# Nixie_Clock.net
KiCad netlist of a schematic drawn in EAGLE
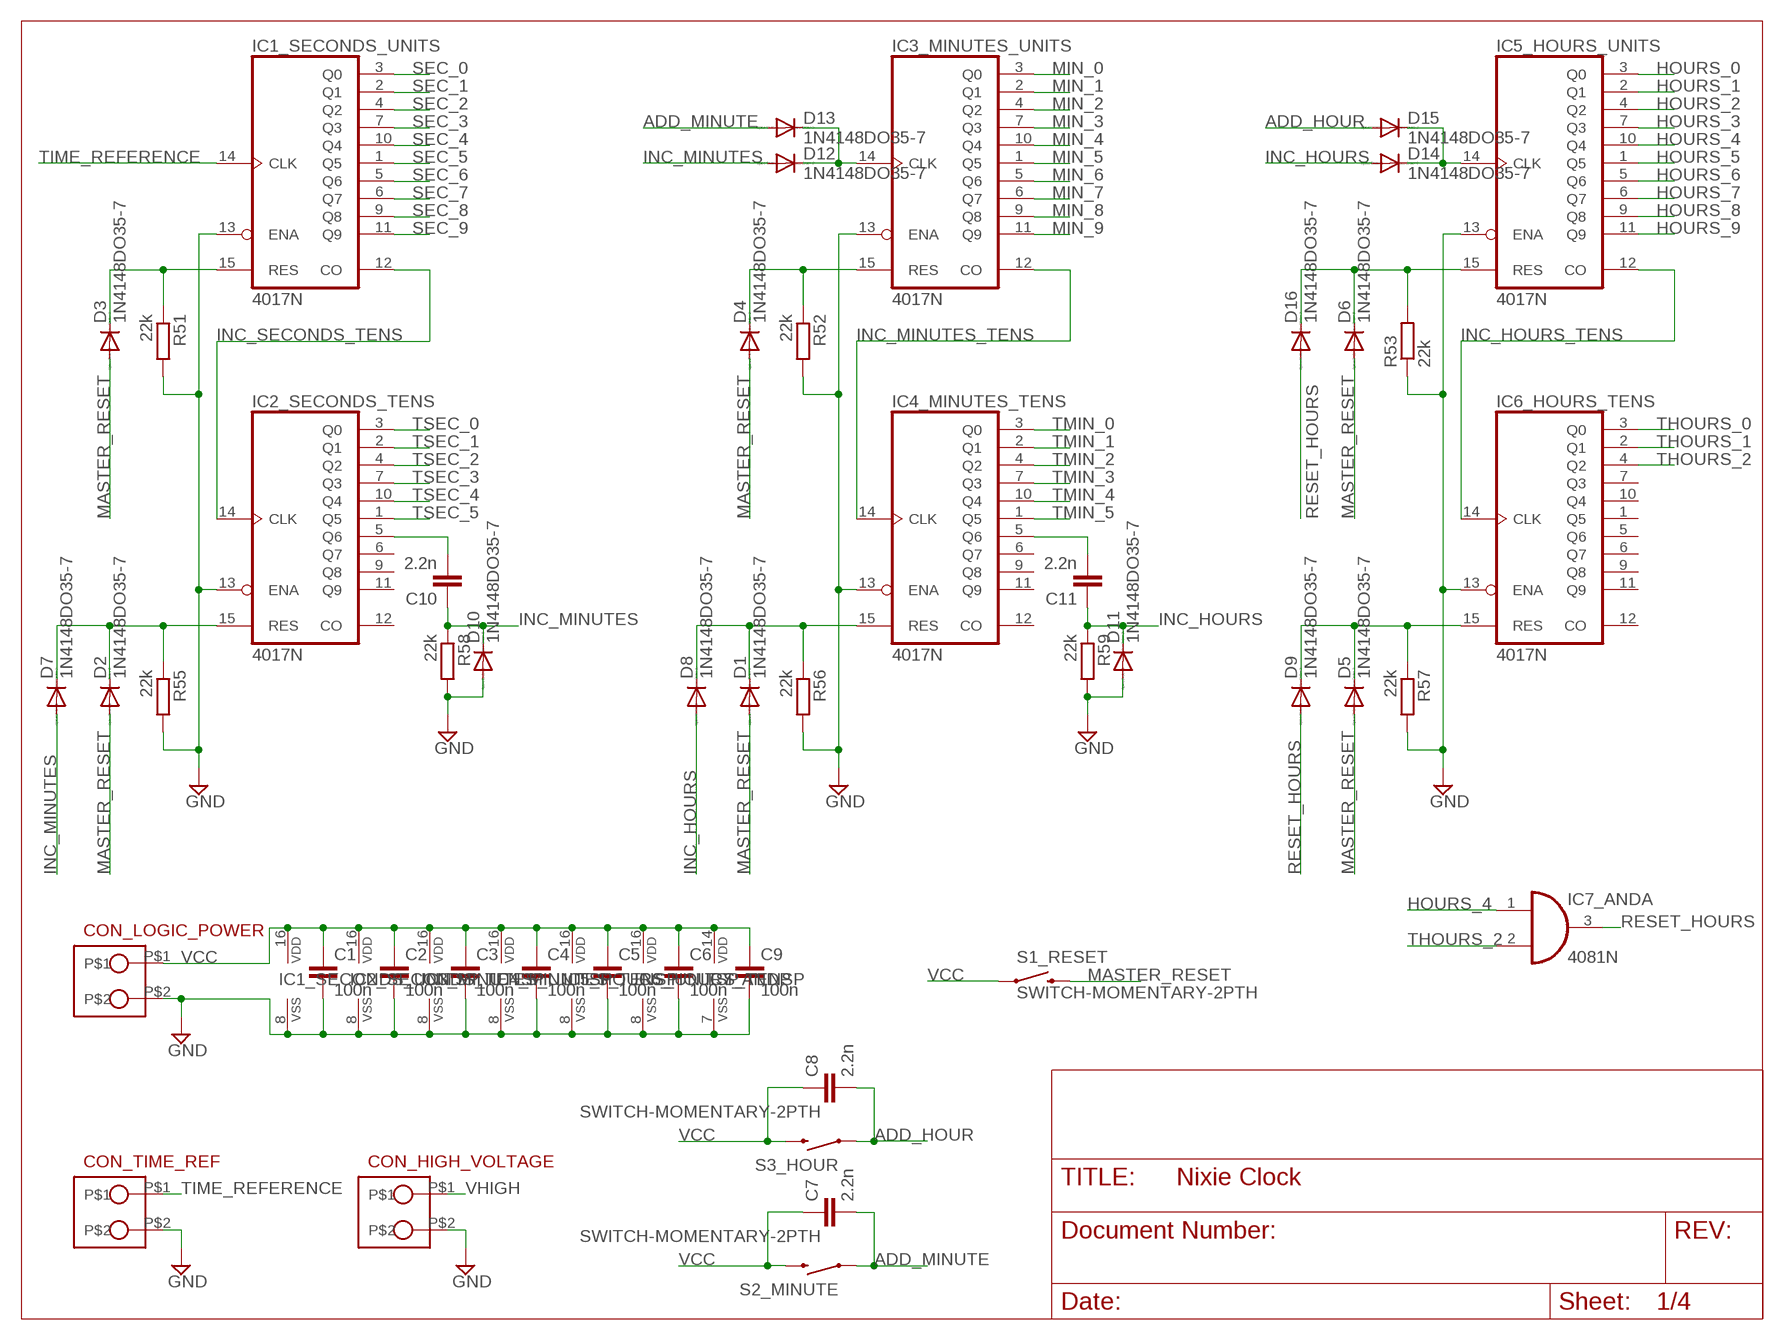
[diagram p0: schematic, sheet 1]
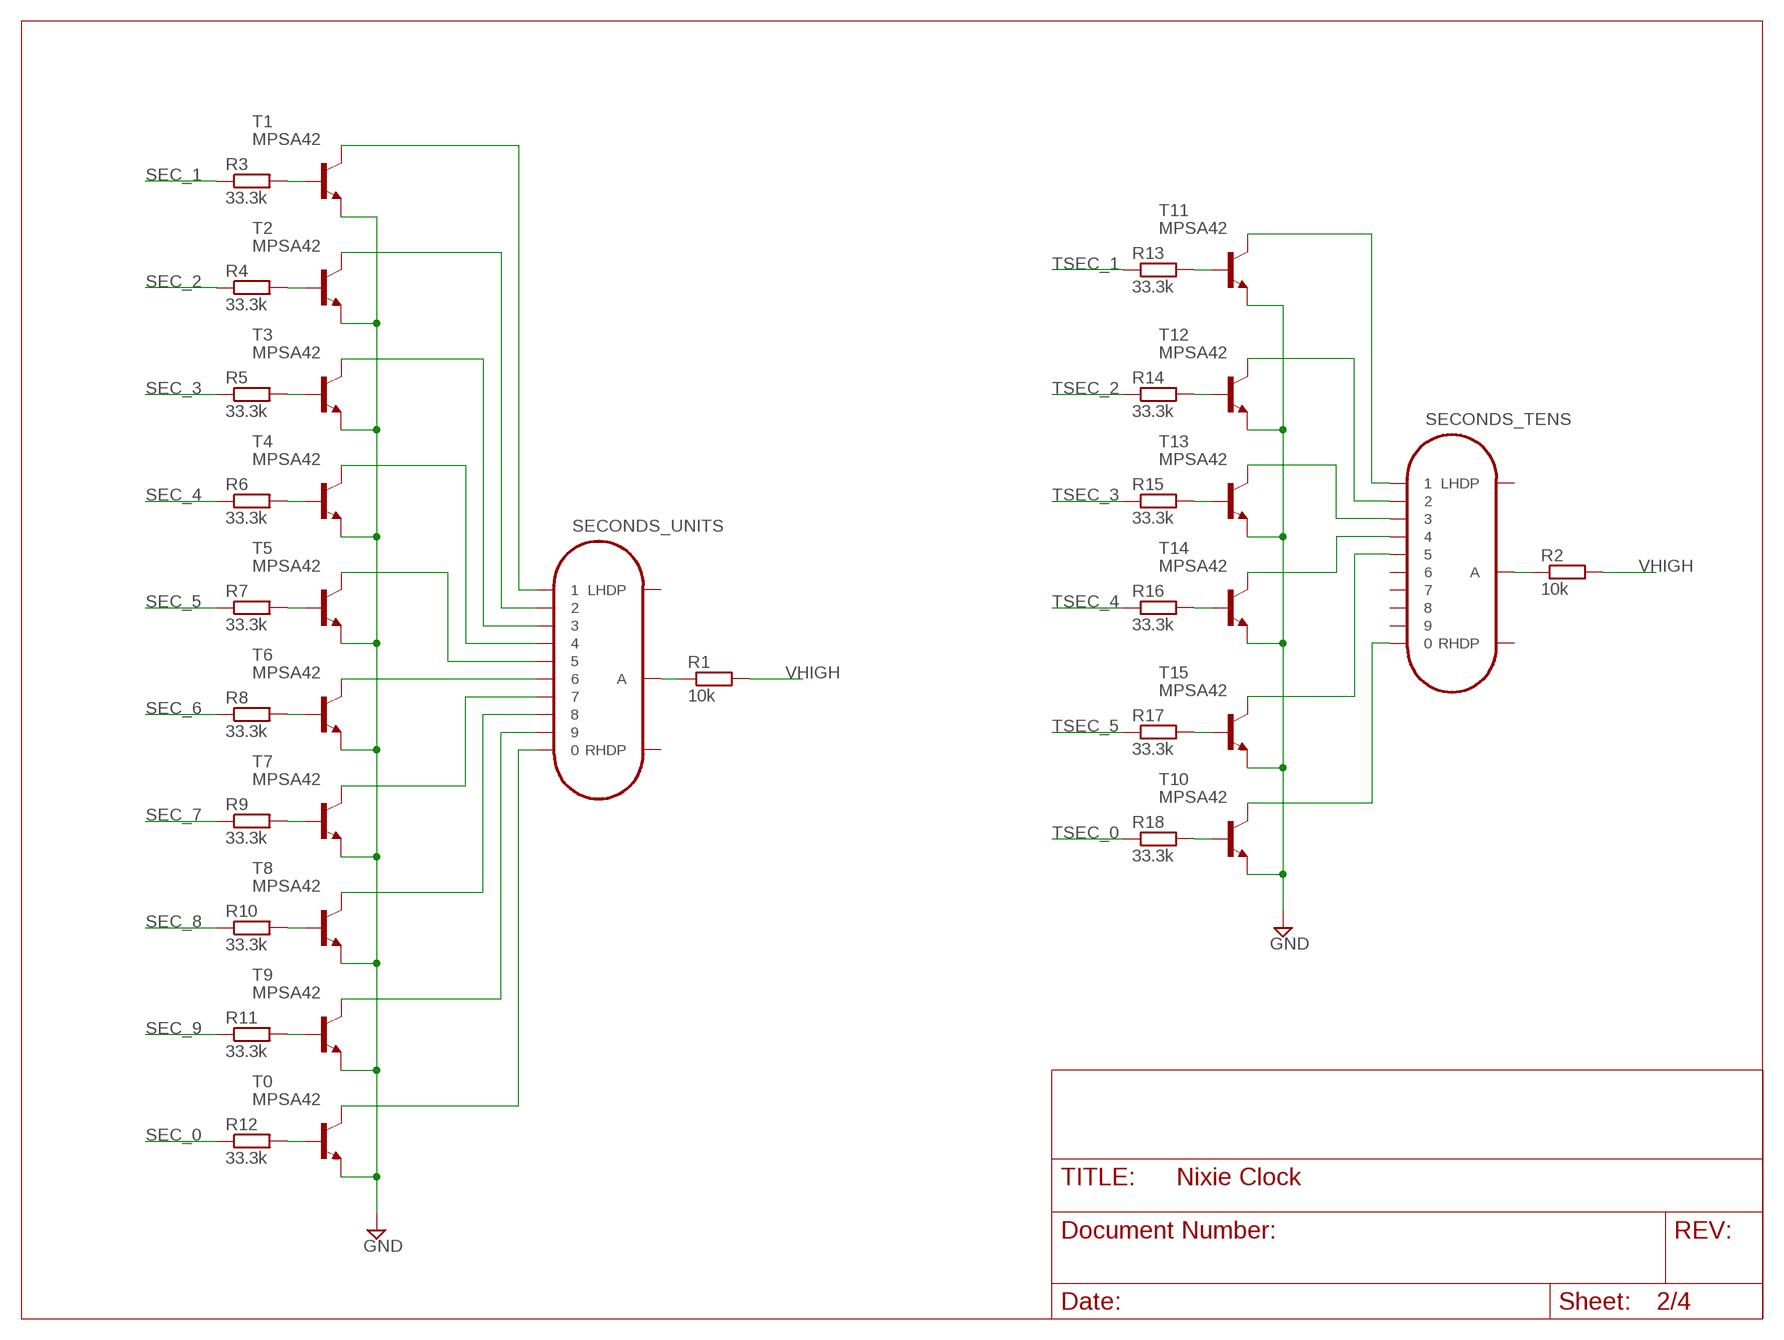
[diagram p1: schematic, sheet 2]
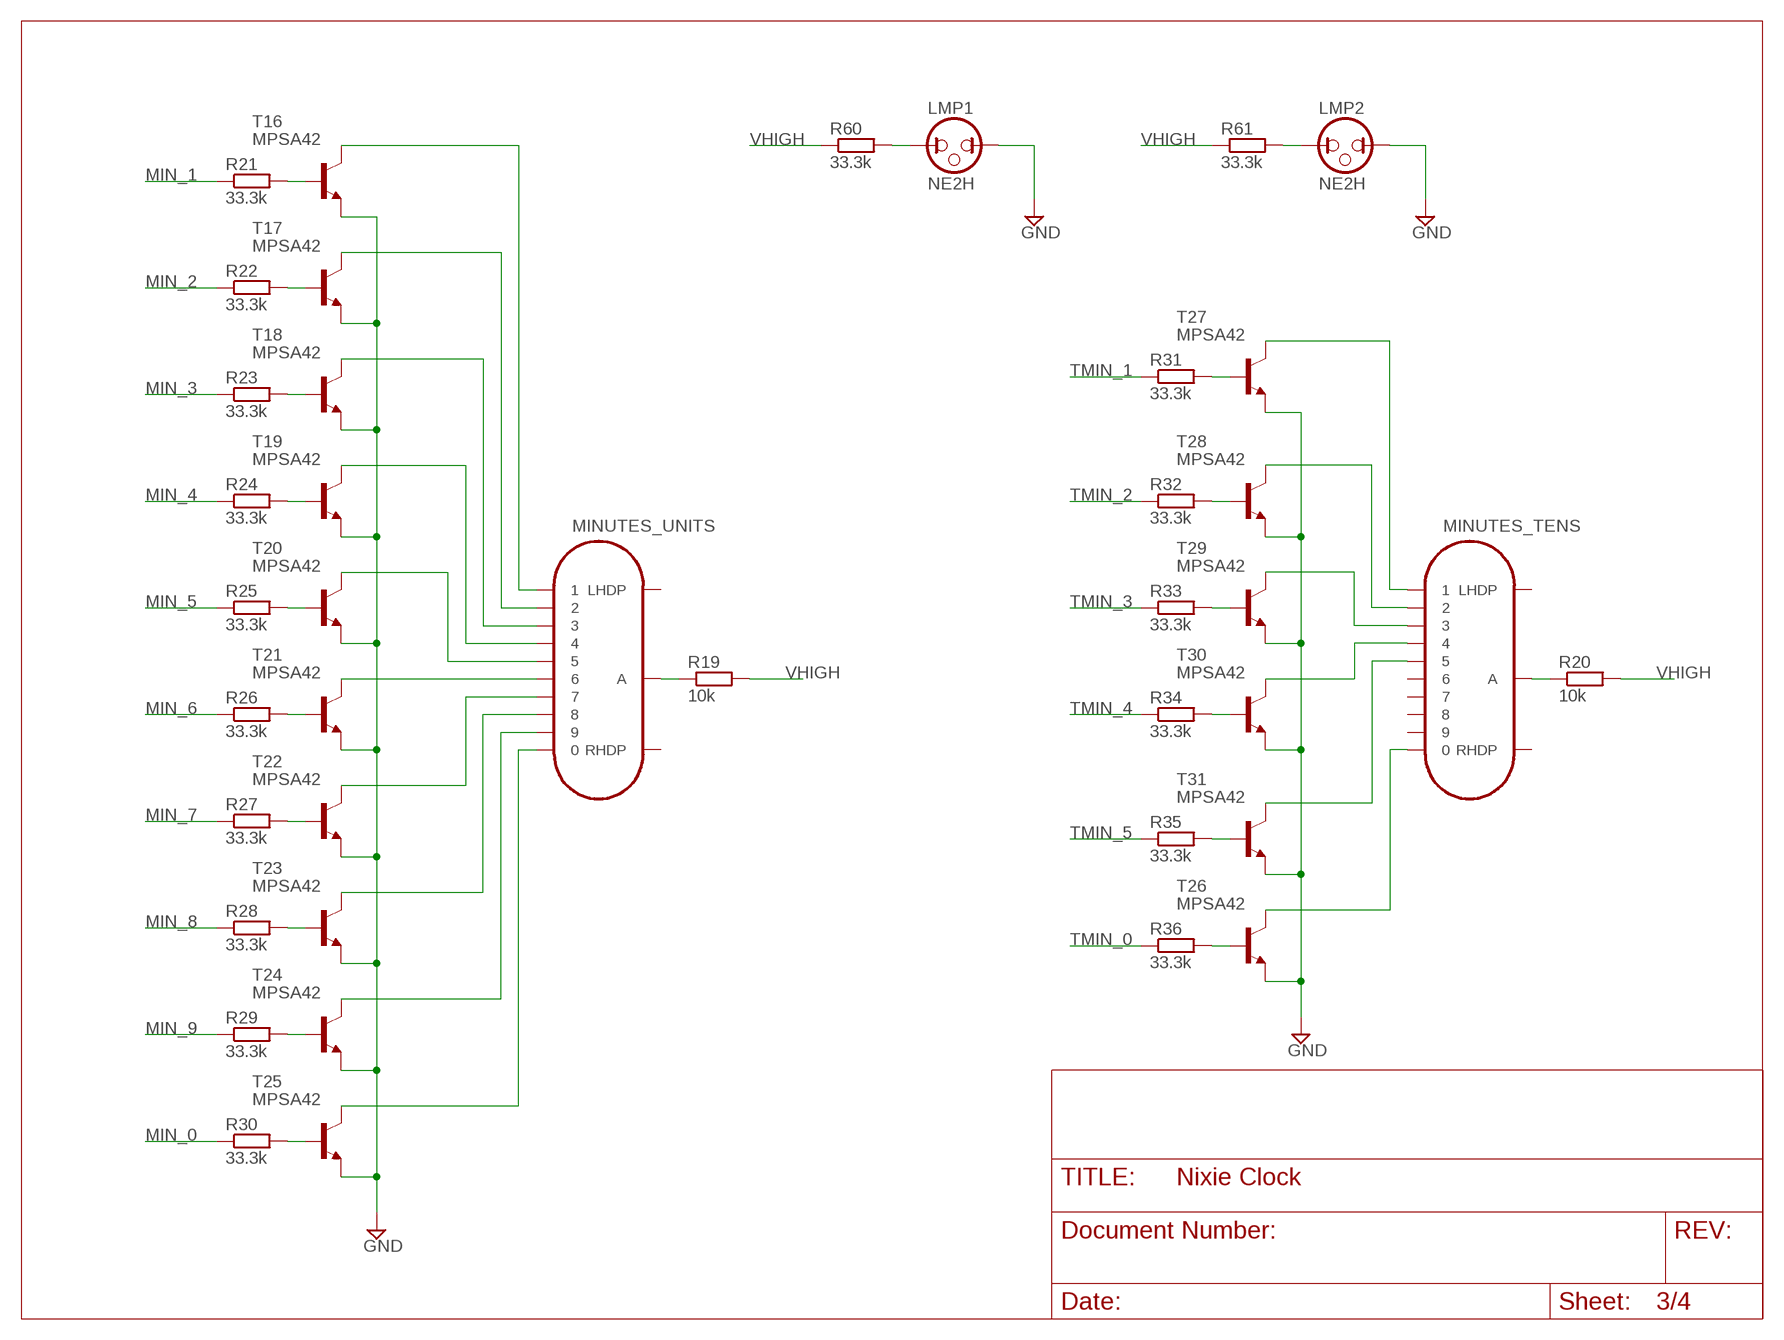
[diagram p2: schematic, sheet 3]
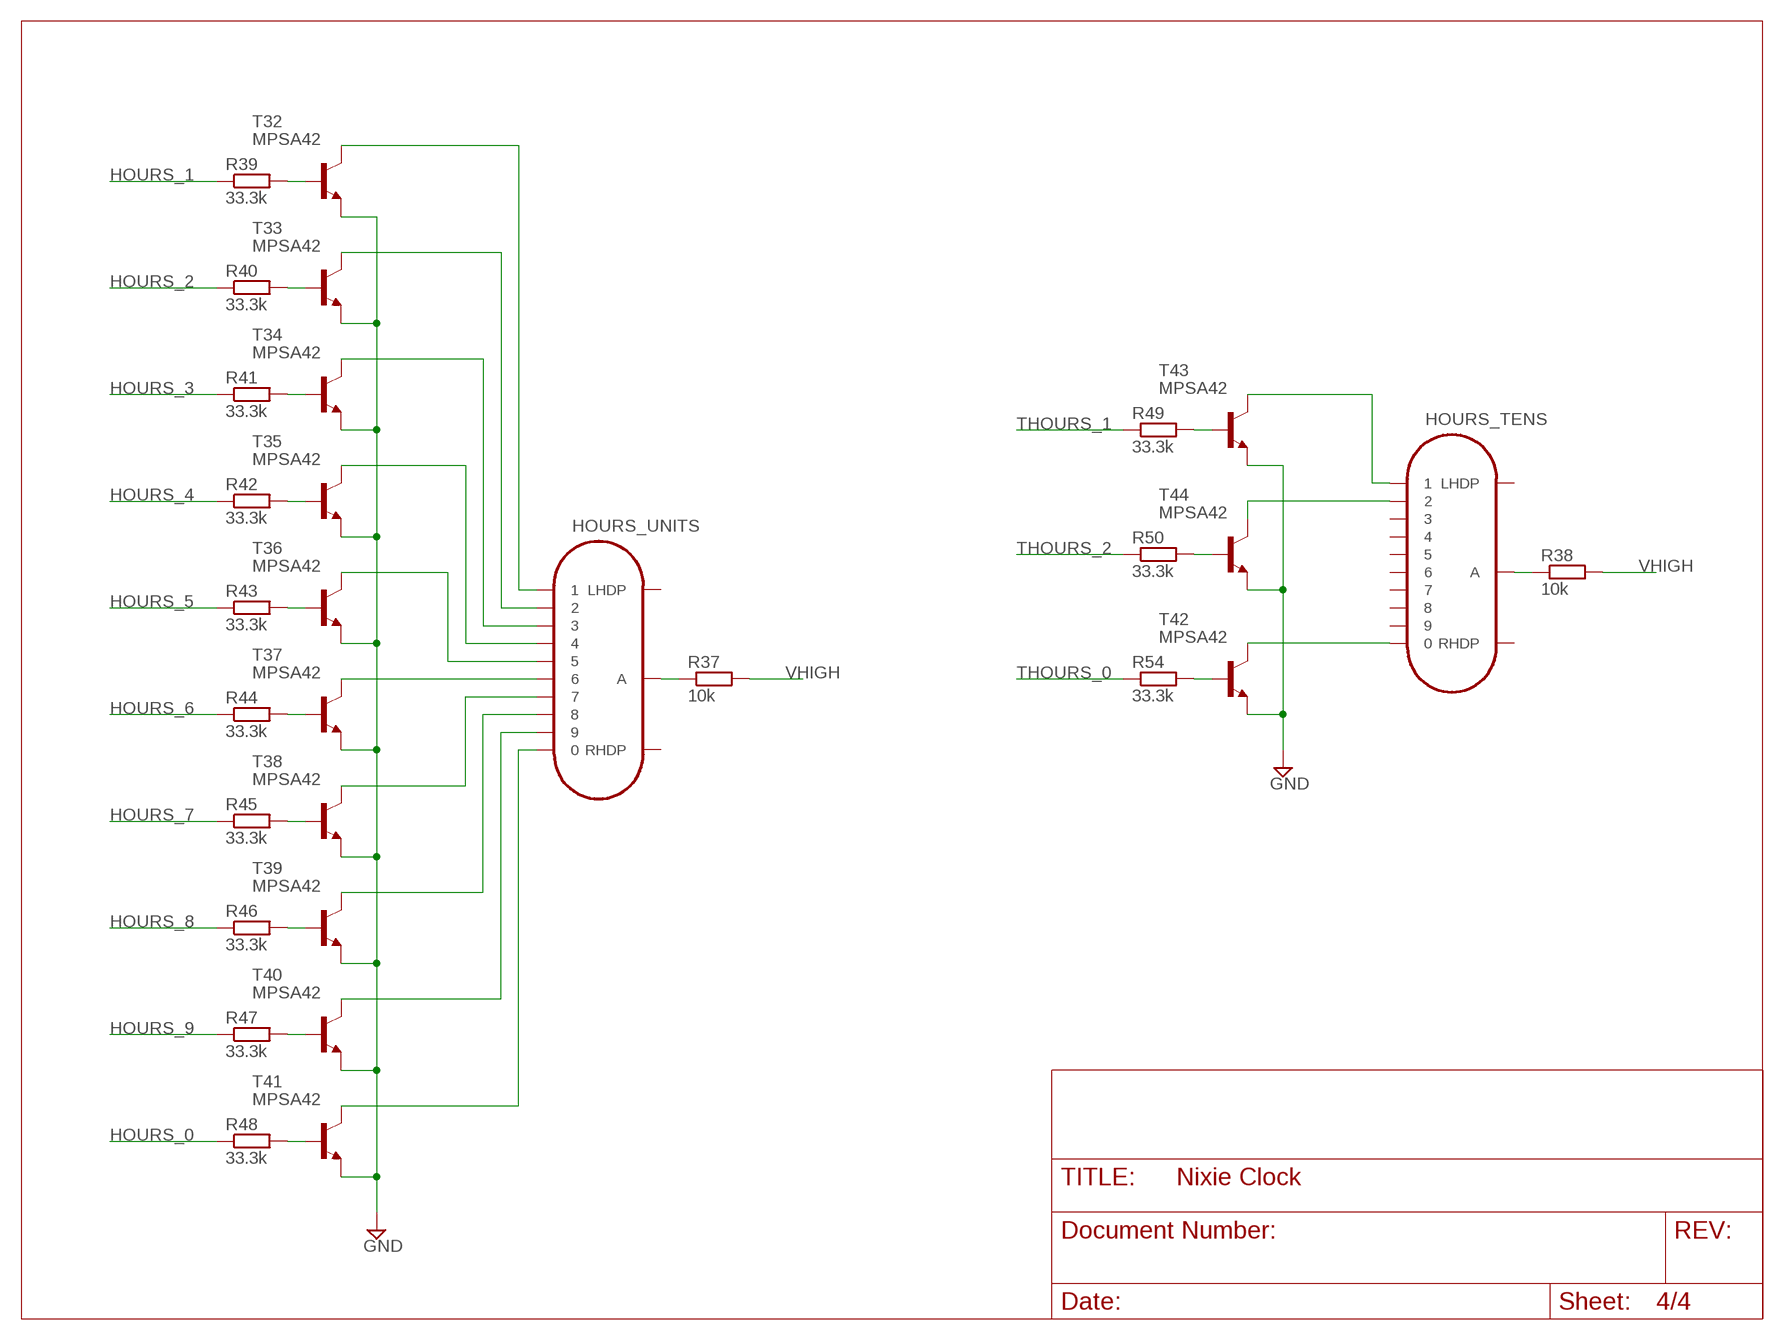
[diagram p3: schematic, sheet 4]

(export (version "E")
  (design (tool "Eeschema 10.0.6"))
  (components
    (comp (ref "HOURS_TENS")
      (value "IN-14BIG_PADS")
      (footprint "eagle-import:IN-14-BIG-PADS")
      (libsource (lib "eagle-import") (part "IN-14BIG_PADS"))
    )
    (comp (ref "HOURS_UNITS")
      (value "IN-14BIG_PADS")
      (footprint "eagle-import:IN-14-BIG-PADS")
      (libsource (lib "eagle-import") (part "IN-14BIG_PADS"))
    )
    (comp (ref "R37")
      (value "10k")
      (footprint "eagle-import:0207_2V")
      (libsource (lib "eagle-import") (part "R-EU_0207/2V"))
    )
    (comp (ref "R38")
      (value "10k")
      (footprint "eagle-import:0207_2V")
      (libsource (lib "eagle-import") (part "R-EU_0207/2V"))
    )
    (comp (ref "R39")
      (value "33.3k")
      (footprint "eagle-import:0207_10")
      (libsource (lib "eagle-import") (part "R-EU_0207/10"))
    )
    (comp (ref "R40")
      (value "33.3k")
      (footprint "eagle-import:0207_10")
      (libsource (lib "eagle-import") (part "R-EU_0207/10"))
    )
    (comp (ref "R41")
      (value "33.3k")
      (footprint "eagle-import:0207_10")
      (libsource (lib "eagle-import") (part "R-EU_0207/10"))
    )
    (comp (ref "R42")
      (value "33.3k")
      (footprint "eagle-import:0207_10")
      (libsource (lib "eagle-import") (part "R-EU_0207/10"))
    )
    (comp (ref "R43")
      (value "33.3k")
      (footprint "eagle-import:0207_10")
      (libsource (lib "eagle-import") (part "R-EU_0207/10"))
    )
    (comp (ref "R44")
      (value "33.3k")
      (footprint "eagle-import:0207_10")
      (libsource (lib "eagle-import") (part "R-EU_0207/10"))
    )
    (comp (ref "R45")
      (value "33.3k")
      (footprint "eagle-import:0207_10")
      (libsource (lib "eagle-import") (part "R-EU_0207/10"))
    )
    (comp (ref "R46")
      (value "33.3k")
      (footprint "eagle-import:0207_10")
      (libsource (lib "eagle-import") (part "R-EU_0207/10"))
    )
    (comp (ref "R47")
      (value "33.3k")
      (footprint "eagle-import:0207_10")
      (libsource (lib "eagle-import") (part "R-EU_0207/10"))
    )
    (comp (ref "R48")
      (value "33.3k")
      (footprint "eagle-import:0207_10")
      (libsource (lib "eagle-import") (part "R-EU_0207/10"))
    )
    (comp (ref "R49")
      (value "33.3k")
      (footprint "eagle-import:0207_10")
      (libsource (lib "eagle-import") (part "R-EU_0207/10"))
    )
    (comp (ref "R50")
      (value "33.3k")
      (footprint "eagle-import:0207_10")
      (libsource (lib "eagle-import") (part "R-EU_0207/10"))
    )
    (comp (ref "R54")
      (value "33.3k")
      (footprint "eagle-import:0207_10")
      (libsource (lib "eagle-import") (part "R-EU_0207/10"))
    )
    (comp (ref "T32")
      (value "MPSA42")
      (footprint "eagle-import:TO92")
      (libsource (lib "eagle-import") (part "MPSA42"))
    )
    (comp (ref "T33")
      (value "MPSA42")
      (footprint "eagle-import:TO92")
      (libsource (lib "eagle-import") (part "MPSA42"))
    )
    (comp (ref "T34")
      (value "MPSA42")
      (footprint "eagle-import:TO92")
      (libsource (lib "eagle-import") (part "MPSA42"))
    )
    (comp (ref "T35")
      (value "MPSA42")
      (footprint "eagle-import:TO92")
      (libsource (lib "eagle-import") (part "MPSA42"))
    )
    (comp (ref "T36")
      (value "MPSA42")
      (footprint "eagle-import:TO92")
      (libsource (lib "eagle-import") (part "MPSA42"))
    )
    (comp (ref "T37")
      (value "MPSA42")
      (footprint "eagle-import:TO92")
      (libsource (lib "eagle-import") (part "MPSA42"))
    )
    (comp (ref "T38")
      (value "MPSA42")
      (footprint "eagle-import:TO92")
      (libsource (lib "eagle-import") (part "MPSA42"))
    )
    (comp (ref "T39")
      (value "MPSA42")
      (footprint "eagle-import:TO92")
      (libsource (lib "eagle-import") (part "MPSA42"))
    )
    (comp (ref "T40")
      (value "MPSA42")
      (footprint "eagle-import:TO92")
      (libsource (lib "eagle-import") (part "MPSA42"))
    )
    (comp (ref "T41")
      (value "MPSA42")
      (footprint "eagle-import:TO92")
      (libsource (lib "eagle-import") (part "MPSA42"))
    )
    (comp (ref "T42")
      (value "MPSA42")
      (footprint "eagle-import:TO92")
      (libsource (lib "eagle-import") (part "MPSA42"))
    )
    (comp (ref "T43")
      (value "MPSA42")
      (footprint "eagle-import:TO92")
      (libsource (lib "eagle-import") (part "MPSA42"))
    )
    (comp (ref "T44")
      (value "MPSA42")
      (footprint "eagle-import:TO92")
      (libsource (lib "eagle-import") (part "MPSA42"))
    )
    (comp (ref "R1")
      (value "10k")
      (footprint "eagle-import:0207_2V")
      (libsource (lib "eagle-import") (part "R-EU_0207/2V"))
    )
    (comp (ref "R2")
      (value "10k")
      (footprint "eagle-import:0207_2V")
      (libsource (lib "eagle-import") (part "R-EU_0207/2V"))
    )
    (comp (ref "R3")
      (value "33.3k")
      (footprint "eagle-import:0207_10")
      (libsource (lib "eagle-import") (part "R-EU_0207/10"))
    )
    (comp (ref "R4")
      (value "33.3k")
      (footprint "eagle-import:0207_10")
      (libsource (lib "eagle-import") (part "R-EU_0207/10"))
    )
    (comp (ref "R5")
      (value "33.3k")
      (footprint "eagle-import:0207_10")
      (libsource (lib "eagle-import") (part "R-EU_0207/10"))
    )
    (comp (ref "R6")
      (value "33.3k")
      (footprint "eagle-import:0207_10")
      (libsource (lib "eagle-import") (part "R-EU_0207/10"))
    )
    (comp (ref "R7")
      (value "33.3k")
      (footprint "eagle-import:0207_10")
      (libsource (lib "eagle-import") (part "R-EU_0207/10"))
    )
    (comp (ref "R8")
      (value "33.3k")
      (footprint "eagle-import:0207_10")
      (libsource (lib "eagle-import") (part "R-EU_0207/10"))
    )
    (comp (ref "R9")
      (value "33.3k")
      (footprint "eagle-import:0207_10")
      (libsource (lib "eagle-import") (part "R-EU_0207/10"))
    )
    (comp (ref "R10")
      (value "33.3k")
      (footprint "eagle-import:0207_10")
      (libsource (lib "eagle-import") (part "R-EU_0207/10"))
    )
    (comp (ref "R11")
      (value "33.3k")
      (footprint "eagle-import:0207_10")
      (libsource (lib "eagle-import") (part "R-EU_0207/10"))
    )
    (comp (ref "R12")
      (value "33.3k")
      (footprint "eagle-import:0207_10")
      (libsource (lib "eagle-import") (part "R-EU_0207/10"))
    )
    (comp (ref "R13")
      (value "33.3k")
      (footprint "eagle-import:0207_10")
      (libsource (lib "eagle-import") (part "R-EU_0207/10"))
    )
    (comp (ref "R14")
      (value "33.3k")
      (footprint "eagle-import:0207_10")
      (libsource (lib "eagle-import") (part "R-EU_0207/10"))
    )
    (comp (ref "R15")
      (value "33.3k")
      (footprint "eagle-import:0207_10")
      (libsource (lib "eagle-import") (part "R-EU_0207/10"))
    )
    (comp (ref "R16")
      (value "33.3k")
      (footprint "eagle-import:0207_10")
      (libsource (lib "eagle-import") (part "R-EU_0207/10"))
    )
    (comp (ref "R17")
      (value "33.3k")
      (footprint "eagle-import:0207_10")
      (libsource (lib "eagle-import") (part "R-EU_0207/10"))
    )
    (comp (ref "R18")
      (value "33.3k")
      (footprint "eagle-import:0207_10")
      (libsource (lib "eagle-import") (part "R-EU_0207/10"))
    )
    (comp (ref "SECONDS_TENS")
      (value "IN-14BIG_PADS")
      (footprint "eagle-import:IN-14-BIG-PADS")
      (libsource (lib "eagle-import") (part "IN-14BIG_PADS"))
    )
    (comp (ref "SECONDS_UNITS")
      (value "IN-14BIG_PADS")
      (footprint "eagle-import:IN-14-BIG-PADS")
      (libsource (lib "eagle-import") (part "IN-14BIG_PADS"))
    )
    (comp (ref "T0")
      (value "MPSA42")
      (footprint "eagle-import:TO92")
      (libsource (lib "eagle-import") (part "MPSA42"))
    )
    (comp (ref "T1")
      (value "MPSA42")
      (footprint "eagle-import:TO92")
      (libsource (lib "eagle-import") (part "MPSA42"))
    )
    (comp (ref "T2")
      (value "MPSA42")
      (footprint "eagle-import:TO92")
      (libsource (lib "eagle-import") (part "MPSA42"))
    )
    (comp (ref "T3")
      (value "MPSA42")
      (footprint "eagle-import:TO92")
      (libsource (lib "eagle-import") (part "MPSA42"))
    )
    (comp (ref "T4")
      (value "MPSA42")
      (footprint "eagle-import:TO92")
      (libsource (lib "eagle-import") (part "MPSA42"))
    )
    (comp (ref "T5")
      (value "MPSA42")
      (footprint "eagle-import:TO92")
      (libsource (lib "eagle-import") (part "MPSA42"))
    )
    (comp (ref "T6")
      (value "MPSA42")
      (footprint "eagle-import:TO92")
      (libsource (lib "eagle-import") (part "MPSA42"))
    )
    (comp (ref "T7")
      (value "MPSA42")
      (footprint "eagle-import:TO92")
      (libsource (lib "eagle-import") (part "MPSA42"))
    )
    (comp (ref "T8")
      (value "MPSA42")
      (footprint "eagle-import:TO92")
      (libsource (lib "eagle-import") (part "MPSA42"))
    )
    (comp (ref "T9")
      (value "MPSA42")
      (footprint "eagle-import:TO92")
      (libsource (lib "eagle-import") (part "MPSA42"))
    )
    (comp (ref "T10")
      (value "MPSA42")
      (footprint "eagle-import:TO92")
      (libsource (lib "eagle-import") (part "MPSA42"))
    )
    (comp (ref "T11")
      (value "MPSA42")
      (footprint "eagle-import:TO92")
      (libsource (lib "eagle-import") (part "MPSA42"))
    )
    (comp (ref "T12")
      (value "MPSA42")
      (footprint "eagle-import:TO92")
      (libsource (lib "eagle-import") (part "MPSA42"))
    )
    (comp (ref "T13")
      (value "MPSA42")
      (footprint "eagle-import:TO92")
      (libsource (lib "eagle-import") (part "MPSA42"))
    )
    (comp (ref "T14")
      (value "MPSA42")
      (footprint "eagle-import:TO92")
      (libsource (lib "eagle-import") (part "MPSA42"))
    )
    (comp (ref "T15")
      (value "MPSA42")
      (footprint "eagle-import:TO92")
      (libsource (lib "eagle-import") (part "MPSA42"))
    )
    (comp (ref "LMP1")
      (value "NE2H")
      (footprint "eagle-import:NEON_LAMP_0.1_INCH")
      (libsource (lib "eagle-import") (part "NEON_LAMP"))
    )
    (comp (ref "LMP2")
      (value "NE2H")
      (footprint "eagle-import:NEON_LAMP_0.1_INCH")
      (libsource (lib "eagle-import") (part "NEON_LAMP"))
    )
    (comp (ref "MINUTES_TENS")
      (value "IN-14BIG_PADS")
      (footprint "eagle-import:IN-14-BIG-PADS")
      (libsource (lib "eagle-import") (part "IN-14BIG_PADS"))
    )
    (comp (ref "MINUTES_UNITS")
      (value "IN-14BIG_PADS")
      (footprint "eagle-import:IN-14-BIG-PADS")
      (libsource (lib "eagle-import") (part "IN-14BIG_PADS"))
    )
    (comp (ref "R19")
      (value "10k")
      (footprint "eagle-import:0207_2V")
      (libsource (lib "eagle-import") (part "R-EU_0207/2V"))
    )
    (comp (ref "R20")
      (value "10k")
      (footprint "eagle-import:0207_2V")
      (libsource (lib "eagle-import") (part "R-EU_0207/2V"))
    )
    (comp (ref "R21")
      (value "33.3k")
      (footprint "eagle-import:0207_10")
      (libsource (lib "eagle-import") (part "R-EU_0207/10"))
    )
    (comp (ref "R22")
      (value "33.3k")
      (footprint "eagle-import:0207_10")
      (libsource (lib "eagle-import") (part "R-EU_0207/10"))
    )
    (comp (ref "R23")
      (value "33.3k")
      (footprint "eagle-import:0207_10")
      (libsource (lib "eagle-import") (part "R-EU_0207/10"))
    )
    (comp (ref "R24")
      (value "33.3k")
      (footprint "eagle-import:0207_10")
      (libsource (lib "eagle-import") (part "R-EU_0207/10"))
    )
    (comp (ref "R25")
      (value "33.3k")
      (footprint "eagle-import:0207_10")
      (libsource (lib "eagle-import") (part "R-EU_0207/10"))
    )
    (comp (ref "R26")
      (value "33.3k")
      (footprint "eagle-import:0207_10")
      (libsource (lib "eagle-import") (part "R-EU_0207/10"))
    )
    (comp (ref "R27")
      (value "33.3k")
      (footprint "eagle-import:0207_10")
      (libsource (lib "eagle-import") (part "R-EU_0207/10"))
    )
    (comp (ref "R28")
      (value "33.3k")
      (footprint "eagle-import:0207_10")
      (libsource (lib "eagle-import") (part "R-EU_0207/10"))
    )
    (comp (ref "R29")
      (value "33.3k")
      (footprint "eagle-import:0207_10")
      (libsource (lib "eagle-import") (part "R-EU_0207/10"))
    )
    (comp (ref "R30")
      (value "33.3k")
      (footprint "eagle-import:0207_10")
      (libsource (lib "eagle-import") (part "R-EU_0207/10"))
    )
    (comp (ref "R31")
      (value "33.3k")
      (footprint "eagle-import:0207_10")
      (libsource (lib "eagle-import") (part "R-EU_0207/10"))
    )
    (comp (ref "R32")
      (value "33.3k")
      (footprint "eagle-import:0207_10")
      (libsource (lib "eagle-import") (part "R-EU_0207/10"))
    )
    (comp (ref "R33")
      (value "33.3k")
      (footprint "eagle-import:0207_10")
      (libsource (lib "eagle-import") (part "R-EU_0207/10"))
    )
    (comp (ref "R34")
      (value "33.3k")
      (footprint "eagle-import:0207_10")
      (libsource (lib "eagle-import") (part "R-EU_0207/10"))
    )
    (comp (ref "R35")
      (value "33.3k")
      (footprint "eagle-import:0207_10")
      (libsource (lib "eagle-import") (part "R-EU_0207/10"))
    )
    (comp (ref "R36")
      (value "33.3k")
      (footprint "eagle-import:0207_10")
      (libsource (lib "eagle-import") (part "R-EU_0207/10"))
    )
    (comp (ref "R60")
      (value "33.3k")
      (footprint "eagle-import:0207_2V")
      (libsource (lib "eagle-import") (part "R-EU_0207/2V"))
    )
    (comp (ref "R61")
      (value "33.3k")
      (footprint "eagle-import:0207_2V")
      (libsource (lib "eagle-import") (part "R-EU_0207/2V"))
    )
    (comp (ref "T16")
      (value "MPSA42")
      (footprint "eagle-import:TO92")
      (libsource (lib "eagle-import") (part "MPSA42"))
    )
    (comp (ref "T17")
      (value "MPSA42")
      (footprint "eagle-import:TO92")
      (libsource (lib "eagle-import") (part "MPSA42"))
    )
    (comp (ref "T18")
      (value "MPSA42")
      (footprint "eagle-import:TO92")
      (libsource (lib "eagle-import") (part "MPSA42"))
    )
    (comp (ref "T19")
      (value "MPSA42")
      (footprint "eagle-import:TO92")
      (libsource (lib "eagle-import") (part "MPSA42"))
    )
    (comp (ref "T20")
      (value "MPSA42")
      (footprint "eagle-import:TO92")
      (libsource (lib "eagle-import") (part "MPSA42"))
    )
    (comp (ref "T21")
      (value "MPSA42")
      (footprint "eagle-import:TO92")
      (libsource (lib "eagle-import") (part "MPSA42"))
    )
    (comp (ref "T22")
      (value "MPSA42")
      (footprint "eagle-import:TO92")
      (libsource (lib "eagle-import") (part "MPSA42"))
    )
    (comp (ref "T23")
      (value "MPSA42")
      (footprint "eagle-import:TO92")
      (libsource (lib "eagle-import") (part "MPSA42"))
    )
    (comp (ref "T24")
      (value "MPSA42")
      (footprint "eagle-import:TO92")
      (libsource (lib "eagle-import") (part "MPSA42"))
    )
    (comp (ref "T25")
      (value "MPSA42")
      (footprint "eagle-import:TO92")
      (libsource (lib "eagle-import") (part "MPSA42"))
    )
    (comp (ref "T26")
      (value "MPSA42")
      (footprint "eagle-import:TO92")
      (libsource (lib "eagle-import") (part "MPSA42"))
    )
    (comp (ref "T27")
      (value "MPSA42")
      (footprint "eagle-import:TO92")
      (libsource (lib "eagle-import") (part "MPSA42"))
    )
    (comp (ref "T28")
      (value "MPSA42")
      (footprint "eagle-import:TO92")
      (libsource (lib "eagle-import") (part "MPSA42"))
    )
    (comp (ref "T29")
      (value "MPSA42")
      (footprint "eagle-import:TO92")
      (libsource (lib "eagle-import") (part "MPSA42"))
    )
    (comp (ref "T30")
      (value "MPSA42")
      (footprint "eagle-import:TO92")
      (libsource (lib "eagle-import") (part "MPSA42"))
    )
    (comp (ref "T31")
      (value "MPSA42")
      (footprint "eagle-import:TO92")
      (libsource (lib "eagle-import") (part "MPSA42"))
    )
    (comp (ref "C1")
      (value "100n")
      (footprint "eagle-import:C050-030X075")
      (libsource (lib "eagle-import") (part "C-EU050-030X075"))
    )
    (comp (ref "C2")
      (value "100n")
      (footprint "eagle-import:C050-030X075")
      (libsource (lib "eagle-import") (part "C-EU050-030X075"))
    )
    (comp (ref "C3")
      (value "100n")
      (footprint "eagle-import:C050-030X075")
      (libsource (lib "eagle-import") (part "C-EU050-030X075"))
    )
    (comp (ref "C4")
      (value "100n")
      (footprint "eagle-import:C050-030X075")
      (libsource (lib "eagle-import") (part "C-EU050-030X075"))
    )
    (comp (ref "C5")
      (value "100n")
      (footprint "eagle-import:C050-030X075")
      (libsource (lib "eagle-import") (part "C-EU050-030X075"))
    )
    (comp (ref "C6")
      (value "100n")
      (footprint "eagle-import:C050-030X075")
      (libsource (lib "eagle-import") (part "C-EU050-030X075"))
    )
    (comp (ref "C7")
      (value "2.2n")
      (footprint "eagle-import:C050-030X075")
      (libsource (lib "eagle-import") (part "C-EU050-030X075"))
    )
    (comp (ref "C8")
      (value "2.2n")
      (footprint "eagle-import:C050-030X075")
      (libsource (lib "eagle-import") (part "C-EU050-030X075"))
    )
    (comp (ref "C9")
      (value "100n")
      (footprint "eagle-import:C050-030X075")
      (libsource (lib "eagle-import") (part "C-EU050-030X075"))
    )
    (comp (ref "C10")
      (value "2.2n")
      (footprint "eagle-import:C050-030X075")
      (libsource (lib "eagle-import") (part "C-EU050-030X075"))
    )
    (comp (ref "C11")
      (value "2.2n")
      (footprint "eagle-import:C050-030X075")
      (libsource (lib "eagle-import") (part "C-EU050-030X075"))
    )
    (comp (ref "CON_HIGH_VOLTAGE")
      (value "CON_2_SIL")
      (footprint "eagle-import:SIL_2_0.2INCH")
      (libsource (lib "eagle-import") (part "CON_2_SIL"))
    )
    (comp (ref "CON_LOGIC_POWER")
      (value "CON_2_SIL")
      (footprint "eagle-import:SIL_2_0.2INCH")
      (libsource (lib "eagle-import") (part "CON_2_SIL"))
    )
    (comp (ref "CON_TIME_REF")
      (value "CON_2_SIL")
      (footprint "eagle-import:SIL_2_0.2INCH")
      (libsource (lib "eagle-import") (part "CON_2_SIL"))
    )
    (comp (ref "D1")
      (value "1N4148DO35-7")
      (footprint "eagle-import:DO35-7")
      (libsource (lib "eagle-import") (part "1N4148DO35-7"))
    )
    (comp (ref "D2")
      (value "1N4148DO35-7")
      (footprint "eagle-import:DO35-7")
      (libsource (lib "eagle-import") (part "1N4148DO35-7"))
    )
    (comp (ref "D3")
      (value "1N4148DO35-7")
      (footprint "eagle-import:DO35-7")
      (libsource (lib "eagle-import") (part "1N4148DO35-7"))
    )
    (comp (ref "D4")
      (value "1N4148DO35-7")
      (footprint "eagle-import:DO35-7")
      (libsource (lib "eagle-import") (part "1N4148DO35-7"))
    )
    (comp (ref "D5")
      (value "1N4148DO35-7")
      (footprint "eagle-import:DO35-7")
      (libsource (lib "eagle-import") (part "1N4148DO35-7"))
    )
    (comp (ref "D6")
      (value "1N4148DO35-7")
      (footprint "eagle-import:DO35-7")
      (libsource (lib "eagle-import") (part "1N4148DO35-7"))
    )
    (comp (ref "D7")
      (value "1N4148DO35-7")
      (footprint "eagle-import:DO35-7")
      (libsource (lib "eagle-import") (part "1N4148DO35-7"))
    )
    (comp (ref "D8")
      (value "1N4148DO35-7")
      (footprint "eagle-import:DO35-7")
      (libsource (lib "eagle-import") (part "1N4148DO35-7"))
    )
    (comp (ref "D9")
      (value "1N4148DO35-7")
      (footprint "eagle-import:DO35-7")
      (libsource (lib "eagle-import") (part "1N4148DO35-7"))
    )
    (comp (ref "D10")
      (value "1N4148DO35-7")
      (footprint "eagle-import:DO35-7")
      (libsource (lib "eagle-import") (part "1N4148DO35-7"))
    )
    (comp (ref "D11")
      (value "1N4148DO35-7")
      (footprint "eagle-import:DO35-7")
      (libsource (lib "eagle-import") (part "1N4148DO35-7"))
    )
    (comp (ref "D12")
      (value "1N4148DO35-7")
      (footprint "eagle-import:DO35-7")
      (libsource (lib "eagle-import") (part "1N4148DO35-7"))
    )
    (comp (ref "D13")
      (value "1N4148DO35-7")
      (footprint "eagle-import:DO35-7")
      (libsource (lib "eagle-import") (part "1N4148DO35-7"))
    )
    (comp (ref "D14")
      (value "1N4148DO35-7")
      (footprint "eagle-import:DO35-7")
      (libsource (lib "eagle-import") (part "1N4148DO35-7"))
    )
    (comp (ref "D15")
      (value "1N4148DO35-7")
      (footprint "eagle-import:DO35-7")
      (libsource (lib "eagle-import") (part "1N4148DO35-7"))
    )
    (comp (ref "D16")
      (value "1N4148DO35-7")
      (footprint "eagle-import:DO35-7")
      (libsource (lib "eagle-import") (part "1N4148DO35-7"))
    )
    (comp (ref "IC1_SECONDS_UNITS")
      (value "4017N")
      (footprint "eagle-import:DIL16")
      (libsource (lib "eagle-import") (part "4017N"))
    )
    (comp (ref "IC2_SECONDS_TENS")
      (value "4017N")
      (footprint "eagle-import:DIL16")
      (libsource (lib "eagle-import") (part "4017N"))
    )
    (comp (ref "IC3_MINUTES_UNITS")
      (value "4017N")
      (footprint "eagle-import:DIL16")
      (libsource (lib "eagle-import") (part "4017N"))
    )
    (comp (ref "IC4_MINUTES_TENS")
      (value "4017N")
      (footprint "eagle-import:DIL16")
      (libsource (lib "eagle-import") (part "4017N"))
    )
    (comp (ref "IC5_HOURS_UNITS")
      (value "4017N")
      (footprint "eagle-import:DIL16")
      (libsource (lib "eagle-import") (part "4017N"))
    )
    (comp (ref "IC6_HOURS_TENS")
      (value "4017N")
      (footprint "eagle-import:DIL16")
      (libsource (lib "eagle-import") (part "4017N"))
    )
    (comp (ref "IC7_AND")
      (value "4081N")
      (footprint "eagle-import:DIL14")
      (libsource (lib "eagle-import") (part "4081N"))
    )
    (comp (ref "R51")
      (value "22k")
      (footprint "eagle-import:0207_10")
      (libsource (lib "eagle-import") (part "R-EU_0207/10"))
    )
    (comp (ref "R52")
      (value "22k")
      (footprint "eagle-import:0207_10")
      (libsource (lib "eagle-import") (part "R-EU_0207/10"))
    )
    (comp (ref "R53")
      (value "22k")
      (footprint "eagle-import:0207_10")
      (libsource (lib "eagle-import") (part "R-EU_0207/10"))
    )
    (comp (ref "R55")
      (value "22k")
      (footprint "eagle-import:0207_10")
      (libsource (lib "eagle-import") (part "R-EU_0207/10"))
    )
    (comp (ref "R56")
      (value "22k")
      (footprint "eagle-import:0207_10")
      (libsource (lib "eagle-import") (part "R-EU_0207/10"))
    )
    (comp (ref "R57")
      (value "22k")
      (footprint "eagle-import:0207_10")
      (libsource (lib "eagle-import") (part "R-EU_0207/10"))
    )
    (comp (ref "R58")
      (value "22k")
      (footprint "eagle-import:0207_10")
      (libsource (lib "eagle-import") (part "R-EU_0207/10"))
    )
    (comp (ref "R59")
      (value "22k")
      (footprint "eagle-import:0207_10")
      (libsource (lib "eagle-import") (part "R-EU_0207/10"))
    )
    (comp (ref "S1_RESET")
      (value "SWITCH-MOMENTARY-2PTH")
      (footprint "eagle-import:TACTILE-PTH")
      (libsource (lib "eagle-import") (part "SWITCH-MOMENTARY-2PTH"))
    )
    (comp (ref "S2_MINUTE")
      (value "SWITCH-MOMENTARY-2PTH")
      (footprint "eagle-import:TACTILE-PTH")
      (libsource (lib "eagle-import") (part "SWITCH-MOMENTARY-2PTH"))
    )
    (comp (ref "S3_HOUR")
      (value "SWITCH-MOMENTARY-2PTH")
      (footprint "eagle-import:TACTILE-PTH")
      (libsource (lib "eagle-import") (part "SWITCH-MOMENTARY-2PTH"))
    )
  )
  (nets
    (net (code "1") (name "ADD_HOUR") (class "Default")
      (node (ref "C8") (pin "2") (pinfunction "2_2") (pintype "passive"))
      (node (ref "D15") (pin "A") (pinfunction "A_A") (pintype "passive"))
      (node (ref "S3_HOUR") (pin "1") (pinfunction "1_1") (pintype "passive"))
    )
    (net (code "2") (name "ADD_MINUTE") (class "Default")
      (node (ref "C7") (pin "2") (pinfunction "2_2") (pintype "passive"))
      (node (ref "D13") (pin "A") (pinfunction "A_A") (pintype "passive"))
      (node (ref "S2_MINUTE") (pin "1") (pinfunction "1_1") (pintype "passive"))
    )
    (net (code "3") (name "GND") (class "Default")
      (node (ref "C1") (pin "2") (pinfunction "2_2") (pintype "passive"))
      (node (ref "C2") (pin "2") (pinfunction "2_2") (pintype "passive"))
      (node (ref "C3") (pin "2") (pinfunction "2_2") (pintype "passive"))
      (node (ref "C4") (pin "2") (pinfunction "2_2") (pintype "passive"))
      (node (ref "C5") (pin "2") (pinfunction "2_2") (pintype "passive"))
      (node (ref "C6") (pin "2") (pinfunction "2_2") (pintype "passive"))
      (node (ref "C9") (pin "2") (pinfunction "2_2") (pintype "passive"))
      (node (ref "CON_HIGH_VOLTAGE") (pin "P$2") (pinfunction "P$2_P$2") (pintype "bidirectional"))
      (node (ref "CON_LOGIC_POWER") (pin "P$2") (pinfunction "P$2_P$2") (pintype "bidirectional"))
      (node (ref "CON_TIME_REF") (pin "P$2") (pinfunction "P$2_P$2") (pintype "bidirectional"))
      (node (ref "D10") (pin "A") (pinfunction "A_A") (pintype "passive"))
      (node (ref "D11") (pin "A") (pinfunction "A_A") (pintype "passive"))
      (node (ref "IC1_SECONDS_UNITS") (pin "13") (pinfunction "ENA_13") (pintype "input"))
      (node (ref "IC1_SECONDS_UNITS") (pin "8") (pinfunction "VSS_8") (pintype "power_in"))
      (node (ref "IC2_SECONDS_TENS") (pin "13") (pinfunction "ENA_13") (pintype "input"))
      (node (ref "IC2_SECONDS_TENS") (pin "8") (pinfunction "VSS_8") (pintype "power_in"))
      (node (ref "IC3_MINUTES_UNITS") (pin "13") (pinfunction "ENA_13") (pintype "input"))
      (node (ref "IC3_MINUTES_UNITS") (pin "8") (pinfunction "VSS_8") (pintype "power_in"))
      (node (ref "IC4_MINUTES_TENS") (pin "13") (pinfunction "ENA_13") (pintype "input"))
      (node (ref "IC4_MINUTES_TENS") (pin "8") (pinfunction "VSS_8") (pintype "power_in"))
      (node (ref "IC5_HOURS_UNITS") (pin "13") (pinfunction "ENA_13") (pintype "input"))
      (node (ref "IC5_HOURS_UNITS") (pin "8") (pinfunction "VSS_8") (pintype "power_in"))
      (node (ref "IC6_HOURS_TENS") (pin "13") (pinfunction "ENA_13") (pintype "input"))
      (node (ref "IC6_HOURS_TENS") (pin "8") (pinfunction "VSS_8") (pintype "power_in"))
      (node (ref "IC7_AND") (pin "7") (pinfunction "VSS_7") (pintype "power_in"))
      (node (ref "LMP1") (pin "P$2") (pinfunction "2_P$2") (pintype "passive"))
      (node (ref "LMP2") (pin "P$2") (pinfunction "2_P$2") (pintype "passive"))
      (node (ref "R51") (pin "2") (pinfunction "2_2") (pintype "passive"))
      (node (ref "R52") (pin "2") (pinfunction "2_2") (pintype "passive"))
      (node (ref "R53") (pin "1") (pinfunction "1_1") (pintype "passive"))
      (node (ref "R55") (pin "2") (pinfunction "2_2") (pintype "passive"))
      (node (ref "R56") (pin "2") (pinfunction "2_2") (pintype "passive"))
      (node (ref "R57") (pin "2") (pinfunction "2_2") (pintype "passive"))
      (node (ref "R58") (pin "2") (pinfunction "2_2") (pintype "passive"))
      (node (ref "R59") (pin "2") (pinfunction "2_2") (pintype "passive"))
      (node (ref "T0") (pin "1") (pinfunction "E_1") (pintype "passive"))
      (node (ref "T1") (pin "1") (pinfunction "E_1") (pintype "passive"))
      (node (ref "T10") (pin "1") (pinfunction "E_1") (pintype "passive"))
      (node (ref "T11") (pin "1") (pinfunction "E_1") (pintype "passive"))
      (node (ref "T12") (pin "1") (pinfunction "E_1") (pintype "passive"))
      (node (ref "T13") (pin "1") (pinfunction "E_1") (pintype "passive"))
      (node (ref "T14") (pin "1") (pinfunction "E_1") (pintype "passive"))
      (node (ref "T15") (pin "1") (pinfunction "E_1") (pintype "passive"))
      (node (ref "T16") (pin "1") (pinfunction "E_1") (pintype "passive"))
      (node (ref "T17") (pin "1") (pinfunction "E_1") (pintype "passive"))
      (node (ref "T18") (pin "1") (pinfunction "E_1") (pintype "passive"))
      (node (ref "T19") (pin "1") (pinfunction "E_1") (pintype "passive"))
      (node (ref "T2") (pin "1") (pinfunction "E_1") (pintype "passive"))
      (node (ref "T20") (pin "1") (pinfunction "E_1") (pintype "passive"))
      (node (ref "T21") (pin "1") (pinfunction "E_1") (pintype "passive"))
      (node (ref "T22") (pin "1") (pinfunction "E_1") (pintype "passive"))
      (node (ref "T23") (pin "1") (pinfunction "E_1") (pintype "passive"))
      (node (ref "T24") (pin "1") (pinfunction "E_1") (pintype "passive"))
      (node (ref "T25") (pin "1") (pinfunction "E_1") (pintype "passive"))
      (node (ref "T26") (pin "1") (pinfunction "E_1") (pintype "passive"))
      (node (ref "T27") (pin "1") (pinfunction "E_1") (pintype "passive"))
      (node (ref "T28") (pin "1") (pinfunction "E_1") (pintype "passive"))
      (node (ref "T29") (pin "1") (pinfunction "E_1") (pintype "passive"))
      (node (ref "T3") (pin "1") (pinfunction "E_1") (pintype "passive"))
      (node (ref "T30") (pin "1") (pinfunction "E_1") (pintype "passive"))
      (node (ref "T31") (pin "1") (pinfunction "E_1") (pintype "passive"))
      (node (ref "T32") (pin "1") (pinfunction "E_1") (pintype "passive"))
      (node (ref "T33") (pin "1") (pinfunction "E_1") (pintype "passive"))
      (node (ref "T34") (pin "1") (pinfunction "E_1") (pintype "passive"))
      (node (ref "T35") (pin "1") (pinfunction "E_1") (pintype "passive"))
      (node (ref "T36") (pin "1") (pinfunction "E_1") (pintype "passive"))
      (node (ref "T37") (pin "1") (pinfunction "E_1") (pintype "passive"))
      (node (ref "T38") (pin "1") (pinfunction "E_1") (pintype "passive"))
      (node (ref "T39") (pin "1") (pinfunction "E_1") (pintype "passive"))
      (node (ref "T4") (pin "1") (pinfunction "E_1") (pintype "passive"))
      (node (ref "T40") (pin "1") (pinfunction "E_1") (pintype "passive"))
      (node (ref "T41") (pin "1") (pinfunction "E_1") (pintype "passive"))
      (node (ref "T42") (pin "1") (pinfunction "E_1") (pintype "passive"))
      (node (ref "T43") (pin "1") (pinfunction "E_1") (pintype "passive"))
      (node (ref "T44") (pin "1") (pinfunction "E_1") (pintype "passive"))
      (node (ref "T5") (pin "1") (pinfunction "E_1") (pintype "passive"))
      (node (ref "T6") (pin "1") (pinfunction "E_1") (pintype "passive"))
      (node (ref "T7") (pin "1") (pinfunction "E_1") (pintype "passive"))
      (node (ref "T8") (pin "1") (pinfunction "E_1") (pintype "passive"))
      (node (ref "T9") (pin "1") (pinfunction "E_1") (pintype "passive"))
    )
    (net (code "4") (name "HOURS_0") (class "Default")
      (node (ref "IC5_HOURS_UNITS") (pin "3") (pinfunction "Q0_3") (pintype "output"))
      (node (ref "R48") (pin "1") (pinfunction "1_1") (pintype "passive"))
    )
    (net (code "5") (name "HOURS_1") (class "Default")
      (node (ref "IC5_HOURS_UNITS") (pin "2") (pinfunction "Q1_2") (pintype "output"))
      (node (ref "R39") (pin "1") (pinfunction "1_1") (pintype "passive"))
    )
    (net (code "6") (name "HOURS_2") (class "Default")
      (node (ref "IC5_HOURS_UNITS") (pin "4") (pinfunction "Q2_4") (pintype "output"))
      (node (ref "R40") (pin "1") (pinfunction "1_1") (pintype "passive"))
    )
    (net (code "7") (name "HOURS_3") (class "Default")
      (node (ref "IC5_HOURS_UNITS") (pin "7") (pinfunction "Q3_7") (pintype "output"))
      (node (ref "R41") (pin "1") (pinfunction "1_1") (pintype "passive"))
    )
    (net (code "8") (name "HOURS_4") (class "Default")
      (node (ref "IC5_HOURS_UNITS") (pin "10") (pinfunction "Q4_10") (pintype "output"))
      (node (ref "IC7_AND") (pin "1") (pinfunction "I0_1") (pintype "input"))
      (node (ref "R42") (pin "1") (pinfunction "1_1") (pintype "passive"))
    )
    (net (code "9") (name "HOURS_5") (class "Default")
      (node (ref "IC5_HOURS_UNITS") (pin "1") (pinfunction "Q5_1") (pintype "output"))
      (node (ref "R43") (pin "1") (pinfunction "1_1") (pintype "passive"))
    )
    (net (code "10") (name "HOURS_6") (class "Default")
      (node (ref "IC5_HOURS_UNITS") (pin "5") (pinfunction "Q6_5") (pintype "output"))
      (node (ref "R44") (pin "1") (pinfunction "1_1") (pintype "passive"))
    )
    (net (code "11") (name "HOURS_7") (class "Default")
      (node (ref "IC5_HOURS_UNITS") (pin "6") (pinfunction "Q7_6") (pintype "output"))
      (node (ref "R45") (pin "1") (pinfunction "1_1") (pintype "passive"))
    )
    (net (code "12") (name "HOURS_8") (class "Default")
      (node (ref "IC5_HOURS_UNITS") (pin "9") (pinfunction "Q8_9") (pintype "output"))
      (node (ref "R46") (pin "1") (pinfunction "1_1") (pintype "passive"))
    )
    (net (code "13") (name "HOURS_9") (class "Default")
      (node (ref "IC5_HOURS_UNITS") (pin "11") (pinfunction "Q9_11") (pintype "output"))
      (node (ref "R47") (pin "1") (pinfunction "1_1") (pintype "passive"))
    )
    (net (code "14") (name "INC_HOURS") (class "Default")
      (node (ref "C11") (pin "1") (pinfunction "1_1") (pintype "passive"))
      (node (ref "D11") (pin "C") (pinfunction "C_C") (pintype "passive"))
      (node (ref "D14") (pin "A") (pinfunction "A_A") (pintype "passive"))
      (node (ref "D8") (pin "A") (pinfunction "A_A") (pintype "passive"))
      (node (ref "R59") (pin "1") (pinfunction "1_1") (pintype "passive"))
    )
    (net (code "15") (name "INC_HOURS_TENS") (class "Default")
      (node (ref "IC5_HOURS_UNITS") (pin "12") (pinfunction "CO_12") (pintype "output"))
      (node (ref "IC6_HOURS_TENS") (pin "14") (pinfunction "CLK_14") (pintype "input"))
    )
    (net (code "16") (name "INC_MINUTES") (class "Default")
      (node (ref "C10") (pin "1") (pinfunction "1_1") (pintype "passive"))
      (node (ref "D10") (pin "C") (pinfunction "C_C") (pintype "passive"))
      (node (ref "D12") (pin "A") (pinfunction "A_A") (pintype "passive"))
      (node (ref "D7") (pin "A") (pinfunction "A_A") (pintype "passive"))
      (node (ref "R58") (pin "1") (pinfunction "1_1") (pintype "passive"))
    )
    (net (code "17") (name "INC_MINUTES_TENS") (class "Default")
      (node (ref "IC3_MINUTES_UNITS") (pin "12") (pinfunction "CO_12") (pintype "output"))
      (node (ref "IC4_MINUTES_TENS") (pin "14") (pinfunction "CLK_14") (pintype "input"))
    )
    (net (code "18") (name "INC_SECONDS_TENS") (class "Default")
      (node (ref "IC1_SECONDS_UNITS") (pin "12") (pinfunction "CO_12") (pintype "output"))
      (node (ref "IC2_SECONDS_TENS") (pin "14") (pinfunction "CLK_14") (pintype "input"))
    )
    (net (code "19") (name "MASTER_RESET") (class "Default")
      (node (ref "D1") (pin "A") (pinfunction "A_A") (pintype "passive"))
      (node (ref "D2") (pin "A") (pinfunction "A_A") (pintype "passive"))
      (node (ref "D3") (pin "A") (pinfunction "A_A") (pintype "passive"))
      (node (ref "D4") (pin "A") (pinfunction "A_A") (pintype "passive"))
      (node (ref "D5") (pin "A") (pinfunction "A_A") (pintype "passive"))
      (node (ref "D6") (pin "A") (pinfunction "A_A") (pintype "passive"))
      (node (ref "S1_RESET") (pin "3") (pinfunction "2_3") (pintype "passive"))
    )
    (net (code "20") (name "MIN_0") (class "Default")
      (node (ref "IC3_MINUTES_UNITS") (pin "3") (pinfunction "Q0_3") (pintype "output"))
      (node (ref "R30") (pin "1") (pinfunction "1_1") (pintype "passive"))
    )
    (net (code "21") (name "MIN_1") (class "Default")
      (node (ref "IC3_MINUTES_UNITS") (pin "2") (pinfunction "Q1_2") (pintype "output"))
      (node (ref "R21") (pin "1") (pinfunction "1_1") (pintype "passive"))
    )
    (net (code "22") (name "MIN_2") (class "Default")
      (node (ref "IC3_MINUTES_UNITS") (pin "4") (pinfunction "Q2_4") (pintype "output"))
      (node (ref "R22") (pin "1") (pinfunction "1_1") (pintype "passive"))
    )
    (net (code "23") (name "MIN_3") (class "Default")
      (node (ref "IC3_MINUTES_UNITS") (pin "7") (pinfunction "Q3_7") (pintype "output"))
      (node (ref "R23") (pin "1") (pinfunction "1_1") (pintype "passive"))
    )
    (net (code "24") (name "MIN_4") (class "Default")
      (node (ref "IC3_MINUTES_UNITS") (pin "10") (pinfunction "Q4_10") (pintype "output"))
      (node (ref "R24") (pin "1") (pinfunction "1_1") (pintype "passive"))
    )
    (net (code "25") (name "MIN_5") (class "Default")
      (node (ref "IC3_MINUTES_UNITS") (pin "1") (pinfunction "Q5_1") (pintype "output"))
      (node (ref "R25") (pin "1") (pinfunction "1_1") (pintype "passive"))
    )
    (net (code "26") (name "MIN_6") (class "Default")
      (node (ref "IC3_MINUTES_UNITS") (pin "5") (pinfunction "Q6_5") (pintype "output"))
      (node (ref "R26") (pin "1") (pinfunction "1_1") (pintype "passive"))
    )
    (net (code "27") (name "MIN_7") (class "Default")
      (node (ref "IC3_MINUTES_UNITS") (pin "6") (pinfunction "Q7_6") (pintype "output"))
      (node (ref "R27") (pin "1") (pinfunction "1_1") (pintype "passive"))
    )
    (net (code "28") (name "MIN_8") (class "Default")
      (node (ref "IC3_MINUTES_UNITS") (pin "9") (pinfunction "Q8_9") (pintype "output"))
      (node (ref "R28") (pin "1") (pinfunction "1_1") (pintype "passive"))
    )
    (net (code "29") (name "MIN_9") (class "Default")
      (node (ref "IC3_MINUTES_UNITS") (pin "11") (pinfunction "Q9_11") (pintype "output"))
      (node (ref "R29") (pin "1") (pinfunction "1_1") (pintype "passive"))
    )
    (net (code "30") (name "Net-(HOURS_TENS-PadA)") (class "Default")
      (node (ref "HOURS_TENS") (pin "A") (pinfunction "A_A") (pintype "bidirectional"))
      (node (ref "R38") (pin "1") (pinfunction "1_1") (pintype "passive"))
    )
    (net (code "31") (name "Net-(HOURS_UNITS-PadA)") (class "Default")
      (node (ref "HOURS_UNITS") (pin "A") (pinfunction "A_A") (pintype "bidirectional"))
      (node (ref "R37") (pin "1") (pinfunction "1_1") (pintype "passive"))
    )
    (net (code "32") (name "Net-(IC1_SECONDS_UNITSA-RES)") (class "Default")
      (node (ref "D3") (pin "C") (pinfunction "C_C") (pintype "passive"))
      (node (ref "IC1_SECONDS_UNITS") (pin "15") (pinfunction "RES_15") (pintype "input"))
      (node (ref "R51") (pin "1") (pinfunction "1_1") (pintype "passive"))
    )
    (net (code "33") (name "Net-(IC2_SECONDS_TENSA-Q6)") (class "Default")
      (node (ref "C10") (pin "2") (pinfunction "2_2") (pintype "passive"))
      (node (ref "IC2_SECONDS_TENS") (pin "5") (pinfunction "Q6_5") (pintype "output"))
    )
    (net (code "34") (name "Net-(IC2_SECONDS_TENSA-RES)") (class "Default")
      (node (ref "D2") (pin "C") (pinfunction "C_C") (pintype "passive"))
      (node (ref "D7") (pin "C") (pinfunction "C_C") (pintype "passive"))
      (node (ref "IC2_SECONDS_TENS") (pin "15") (pinfunction "RES_15") (pintype "input"))
      (node (ref "R55") (pin "1") (pinfunction "1_1") (pintype "passive"))
    )
    (net (code "35") (name "Net-(IC3_MINUTES_UNITSA-CLK)") (class "Default")
      (node (ref "D12") (pin "C") (pinfunction "C_C") (pintype "passive"))
      (node (ref "D13") (pin "C") (pinfunction "C_C") (pintype "passive"))
      (node (ref "IC3_MINUTES_UNITS") (pin "14") (pinfunction "CLK_14") (pintype "input"))
    )
    (net (code "36") (name "Net-(IC3_MINUTES_UNITSA-RES)") (class "Default")
      (node (ref "D4") (pin "C") (pinfunction "C_C") (pintype "passive"))
      (node (ref "IC3_MINUTES_UNITS") (pin "15") (pinfunction "RES_15") (pintype "input"))
      (node (ref "R52") (pin "1") (pinfunction "1_1") (pintype "passive"))
    )
    (net (code "37") (name "Net-(IC4_MINUTES_TENSA-Q6)") (class "Default")
      (node (ref "C11") (pin "2") (pinfunction "2_2") (pintype "passive"))
      (node (ref "IC4_MINUTES_TENS") (pin "5") (pinfunction "Q6_5") (pintype "output"))
    )
    (net (code "38") (name "Net-(IC4_MINUTES_TENSA-RES)") (class "Default")
      (node (ref "D1") (pin "C") (pinfunction "C_C") (pintype "passive"))
      (node (ref "D8") (pin "C") (pinfunction "C_C") (pintype "passive"))
      (node (ref "IC4_MINUTES_TENS") (pin "15") (pinfunction "RES_15") (pintype "input"))
      (node (ref "R56") (pin "1") (pinfunction "1_1") (pintype "passive"))
    )
    (net (code "39") (name "Net-(IC5_HOURS_UNITSA-CLK)") (class "Default")
      (node (ref "D14") (pin "C") (pinfunction "C_C") (pintype "passive"))
      (node (ref "D15") (pin "C") (pinfunction "C_C") (pintype "passive"))
      (node (ref "IC5_HOURS_UNITS") (pin "14") (pinfunction "CLK_14") (pintype "input"))
    )
    (net (code "40") (name "Net-(IC5_HOURS_UNITSA-RES)") (class "Default")
      (node (ref "D16") (pin "C") (pinfunction "C_C") (pintype "passive"))
      (node (ref "D6") (pin "C") (pinfunction "C_C") (pintype "passive"))
      (node (ref "IC5_HOURS_UNITS") (pin "15") (pinfunction "RES_15") (pintype "input"))
      (node (ref "R53") (pin "2") (pinfunction "2_2") (pintype "passive"))
    )
    (net (code "41") (name "Net-(IC6_HOURS_TENSA-RES)") (class "Default")
      (node (ref "D5") (pin "C") (pinfunction "C_C") (pintype "passive"))
      (node (ref "D9") (pin "C") (pinfunction "C_C") (pintype "passive"))
      (node (ref "IC6_HOURS_TENS") (pin "15") (pinfunction "RES_15") (pintype "input"))
      (node (ref "R57") (pin "1") (pinfunction "1_1") (pintype "passive"))
    )
    (net (code "42") (name "Net-(LMP1-1)") (class "Default")
      (node (ref "LMP1") (pin "P$1") (pinfunction "1_P$1") (pintype "passive"))
      (node (ref "R60") (pin "2") (pinfunction "2_2") (pintype "passive"))
    )
    (net (code "43") (name "Net-(LMP2-1)") (class "Default")
      (node (ref "LMP2") (pin "P$1") (pinfunction "1_P$1") (pintype "passive"))
      (node (ref "R61") (pin "2") (pinfunction "2_2") (pintype "passive"))
    )
    (net (code "44") (name "Net-(MINUTES_TENS-PadA)") (class "Default")
      (node (ref "MINUTES_TENS") (pin "A") (pinfunction "A_A") (pintype "bidirectional"))
      (node (ref "R20") (pin "1") (pinfunction "1_1") (pintype "passive"))
    )
    (net (code "45") (name "Net-(MINUTES_UNITS-PadA)") (class "Default")
      (node (ref "MINUTES_UNITS") (pin "A") (pinfunction "A_A") (pintype "bidirectional"))
      (node (ref "R19") (pin "1") (pinfunction "1_1") (pintype "passive"))
    )
    (net (code "46") (name "Net-(R1-Pad1)") (class "Default")
      (node (ref "R1") (pin "1") (pinfunction "1_1") (pintype "passive"))
      (node (ref "SECONDS_UNITS") (pin "A") (pinfunction "A_A") (pintype "bidirectional"))
    )
    (net (code "47") (name "Net-(R2-Pad1)") (class "Default")
      (node (ref "R2") (pin "1") (pinfunction "1_1") (pintype "passive"))
      (node (ref "SECONDS_TENS") (pin "A") (pinfunction "A_A") (pintype "bidirectional"))
    )
    (net (code "48") (name "Net-(T0-B)") (class "Default")
      (node (ref "R12") (pin "2") (pinfunction "2_2") (pintype "passive"))
      (node (ref "T0") (pin "2") (pinfunction "B_2") (pintype "passive"))
    )
    (net (code "49") (name "Net-(T0-C)") (class "Default")
      (node (ref "SECONDS_UNITS") (pin "0") (pinfunction "0_0") (pintype "bidirectional"))
      (node (ref "T0") (pin "3") (pinfunction "C_3") (pintype "passive"))
    )
    (net (code "50") (name "Net-(T1-B)") (class "Default")
      (node (ref "R3") (pin "2") (pinfunction "2_2") (pintype "passive"))
      (node (ref "T1") (pin "2") (pinfunction "B_2") (pintype "passive"))
    )
    (net (code "51") (name "Net-(T1-C)") (class "Default")
      (node (ref "SECONDS_UNITS") (pin "1") (pinfunction "1_1") (pintype "bidirectional"))
      (node (ref "T1") (pin "3") (pinfunction "C_3") (pintype "passive"))
    )
    (net (code "52") (name "Net-(T2-B)") (class "Default")
      (node (ref "R4") (pin "2") (pinfunction "2_2") (pintype "passive"))
      (node (ref "T2") (pin "2") (pinfunction "B_2") (pintype "passive"))
    )
    (net (code "53") (name "Net-(T2-C)") (class "Default")
      (node (ref "SECONDS_UNITS") (pin "2") (pinfunction "2_2") (pintype "bidirectional"))
      (node (ref "T2") (pin "3") (pinfunction "C_3") (pintype "passive"))
    )
    (net (code "54") (name "Net-(T3-B)") (class "Default")
      (node (ref "R5") (pin "2") (pinfunction "2_2") (pintype "passive"))
      (node (ref "T3") (pin "2") (pinfunction "B_2") (pintype "passive"))
    )
    (net (code "55") (name "Net-(T3-C)") (class "Default")
      (node (ref "SECONDS_UNITS") (pin "3") (pinfunction "3_3") (pintype "bidirectional"))
      (node (ref "T3") (pin "3") (pinfunction "C_3") (pintype "passive"))
    )
    (net (code "56") (name "Net-(T4-B)") (class "Default")
      (node (ref "R6") (pin "2") (pinfunction "2_2") (pintype "passive"))
      (node (ref "T4") (pin "2") (pinfunction "B_2") (pintype "passive"))
    )
    (net (code "57") (name "Net-(T4-C)") (class "Default")
      (node (ref "SECONDS_UNITS") (pin "4") (pinfunction "4_4") (pintype "bidirectional"))
      (node (ref "T4") (pin "3") (pinfunction "C_3") (pintype "passive"))
    )
    (net (code "58") (name "Net-(T5-B)") (class "Default")
      (node (ref "R7") (pin "2") (pinfunction "2_2") (pintype "passive"))
      (node (ref "T5") (pin "2") (pinfunction "B_2") (pintype "passive"))
    )
    (net (code "59") (name "Net-(T5-C)") (class "Default")
      (node (ref "SECONDS_UNITS") (pin "5") (pinfunction "5_5") (pintype "bidirectional"))
      (node (ref "T5") (pin "3") (pinfunction "C_3") (pintype "passive"))
    )
    (net (code "60") (name "Net-(T6-B)") (class "Default")
      (node (ref "R8") (pin "2") (pinfunction "2_2") (pintype "passive"))
      (node (ref "T6") (pin "2") (pinfunction "B_2") (pintype "passive"))
    )
    (net (code "61") (name "Net-(T6-C)") (class "Default")
      (node (ref "SECONDS_UNITS") (pin "6") (pinfunction "6_6") (pintype "bidirectional"))
      (node (ref "T6") (pin "3") (pinfunction "C_3") (pintype "passive"))
    )
    (net (code "62") (name "Net-(T7-B)") (class "Default")
      (node (ref "R9") (pin "2") (pinfunction "2_2") (pintype "passive"))
      (node (ref "T7") (pin "2") (pinfunction "B_2") (pintype "passive"))
    )
    (net (code "63") (name "Net-(T7-C)") (class "Default")
      (node (ref "SECONDS_UNITS") (pin "7") (pinfunction "7_7") (pintype "bidirectional"))
      (node (ref "T7") (pin "3") (pinfunction "C_3") (pintype "passive"))
    )
    (net (code "64") (name "Net-(T8-B)") (class "Default")
      (node (ref "R10") (pin "2") (pinfunction "2_2") (pintype "passive"))
      (node (ref "T8") (pin "2") (pinfunction "B_2") (pintype "passive"))
    )
    (net (code "65") (name "Net-(T8-C)") (class "Default")
      (node (ref "SECONDS_UNITS") (pin "8") (pinfunction "8_8") (pintype "bidirectional"))
      (node (ref "T8") (pin "3") (pinfunction "C_3") (pintype "passive"))
    )
    (net (code "66") (name "Net-(T9-B)") (class "Default")
      (node (ref "R11") (pin "2") (pinfunction "2_2") (pintype "passive"))
      (node (ref "T9") (pin "2") (pinfunction "B_2") (pintype "passive"))
    )
    (net (code "67") (name "Net-(T9-C)") (class "Default")
      (node (ref "SECONDS_UNITS") (pin "9") (pinfunction "9_9") (pintype "bidirectional"))
      (node (ref "T9") (pin "3") (pinfunction "C_3") (pintype "passive"))
    )
    (net (code "68") (name "Net-(T10-B)") (class "Default")
      (node (ref "R18") (pin "2") (pinfunction "2_2") (pintype "passive"))
      (node (ref "T10") (pin "2") (pinfunction "B_2") (pintype "passive"))
    )
    (net (code "69") (name "Net-(T10-C)") (class "Default")
      (node (ref "SECONDS_TENS") (pin "0") (pinfunction "0_0") (pintype "bidirectional"))
      (node (ref "T10") (pin "3") (pinfunction "C_3") (pintype "passive"))
    )
    (net (code "70") (name "Net-(T11-B)") (class "Default")
      (node (ref "R13") (pin "2") (pinfunction "2_2") (pintype "passive"))
      (node (ref "T11") (pin "2") (pinfunction "B_2") (pintype "passive"))
    )
    (net (code "71") (name "Net-(T11-C)") (class "Default")
      (node (ref "SECONDS_TENS") (pin "1") (pinfunction "1_1") (pintype "bidirectional"))
      (node (ref "T11") (pin "3") (pinfunction "C_3") (pintype "passive"))
    )
    (net (code "72") (name "Net-(T12-B)") (class "Default")
      (node (ref "R14") (pin "2") (pinfunction "2_2") (pintype "passive"))
      (node (ref "T12") (pin "2") (pinfunction "B_2") (pintype "passive"))
    )
    (net (code "73") (name "Net-(T12-C)") (class "Default")
      (node (ref "SECONDS_TENS") (pin "2") (pinfunction "2_2") (pintype "bidirectional"))
      (node (ref "T12") (pin "3") (pinfunction "C_3") (pintype "passive"))
    )
    (net (code "74") (name "Net-(T13-B)") (class "Default")
      (node (ref "R15") (pin "2") (pinfunction "2_2") (pintype "passive"))
      (node (ref "T13") (pin "2") (pinfunction "B_2") (pintype "passive"))
    )
    (net (code "75") (name "Net-(T13-C)") (class "Default")
      (node (ref "SECONDS_TENS") (pin "3") (pinfunction "3_3") (pintype "bidirectional"))
      (node (ref "T13") (pin "3") (pinfunction "C_3") (pintype "passive"))
    )
    (net (code "76") (name "Net-(T14-B)") (class "Default")
      (node (ref "R16") (pin "2") (pinfunction "2_2") (pintype "passive"))
      (node (ref "T14") (pin "2") (pinfunction "B_2") (pintype "passive"))
    )
    (net (code "77") (name "Net-(T14-C)") (class "Default")
      (node (ref "SECONDS_TENS") (pin "4") (pinfunction "4_4") (pintype "bidirectional"))
      (node (ref "T14") (pin "3") (pinfunction "C_3") (pintype "passive"))
    )
    (net (code "78") (name "Net-(T15-B)") (class "Default")
      (node (ref "R17") (pin "2") (pinfunction "2_2") (pintype "passive"))
      (node (ref "T15") (pin "2") (pinfunction "B_2") (pintype "passive"))
    )
    (net (code "79") (name "Net-(T15-C)") (class "Default")
      (node (ref "SECONDS_TENS") (pin "5") (pinfunction "5_5") (pintype "bidirectional"))
      (node (ref "T15") (pin "3") (pinfunction "C_3") (pintype "passive"))
    )
    (net (code "80") (name "Net-(T16-B)") (class "Default")
      (node (ref "R21") (pin "2") (pinfunction "2_2") (pintype "passive"))
      (node (ref "T16") (pin "2") (pinfunction "B_2") (pintype "passive"))
    )
    (net (code "81") (name "Net-(T16-C)") (class "Default")
      (node (ref "MINUTES_UNITS") (pin "1") (pinfunction "1_1") (pintype "bidirectional"))
      (node (ref "T16") (pin "3") (pinfunction "C_3") (pintype "passive"))
    )
    (net (code "82") (name "Net-(T17-B)") (class "Default")
      (node (ref "R22") (pin "2") (pinfunction "2_2") (pintype "passive"))
      (node (ref "T17") (pin "2") (pinfunction "B_2") (pintype "passive"))
    )
    (net (code "83") (name "Net-(T17-C)") (class "Default")
      (node (ref "MINUTES_UNITS") (pin "2") (pinfunction "2_2") (pintype "bidirectional"))
      (node (ref "T17") (pin "3") (pinfunction "C_3") (pintype "passive"))
    )
    (net (code "84") (name "Net-(T18-B)") (class "Default")
      (node (ref "R23") (pin "2") (pinfunction "2_2") (pintype "passive"))
      (node (ref "T18") (pin "2") (pinfunction "B_2") (pintype "passive"))
    )
    (net (code "85") (name "Net-(T18-C)") (class "Default")
      (node (ref "MINUTES_UNITS") (pin "3") (pinfunction "3_3") (pintype "bidirectional"))
      (node (ref "T18") (pin "3") (pinfunction "C_3") (pintype "passive"))
    )
    (net (code "86") (name "Net-(T19-B)") (class "Default")
      (node (ref "R24") (pin "2") (pinfunction "2_2") (pintype "passive"))
      (node (ref "T19") (pin "2") (pinfunction "B_2") (pintype "passive"))
    )
    (net (code "87") (name "Net-(T19-C)") (class "Default")
      (node (ref "MINUTES_UNITS") (pin "4") (pinfunction "4_4") (pintype "bidirectional"))
      (node (ref "T19") (pin "3") (pinfunction "C_3") (pintype "passive"))
    )
    (net (code "88") (name "Net-(T20-B)") (class "Default")
      (node (ref "R25") (pin "2") (pinfunction "2_2") (pintype "passive"))
      (node (ref "T20") (pin "2") (pinfunction "B_2") (pintype "passive"))
    )
    (net (code "89") (name "Net-(T20-C)") (class "Default")
      (node (ref "MINUTES_UNITS") (pin "5") (pinfunction "5_5") (pintype "bidirectional"))
      (node (ref "T20") (pin "3") (pinfunction "C_3") (pintype "passive"))
    )
    (net (code "90") (name "Net-(T21-B)") (class "Default")
      (node (ref "R26") (pin "2") (pinfunction "2_2") (pintype "passive"))
      (node (ref "T21") (pin "2") (pinfunction "B_2") (pintype "passive"))
    )
    (net (code "91") (name "Net-(T21-C)") (class "Default")
      (node (ref "MINUTES_UNITS") (pin "6") (pinfunction "6_6") (pintype "bidirectional"))
      (node (ref "T21") (pin "3") (pinfunction "C_3") (pintype "passive"))
    )
    (net (code "92") (name "Net-(T22-B)") (class "Default")
      (node (ref "R27") (pin "2") (pinfunction "2_2") (pintype "passive"))
      (node (ref "T22") (pin "2") (pinfunction "B_2") (pintype "passive"))
    )
    (net (code "93") (name "Net-(T22-C)") (class "Default")
      (node (ref "MINUTES_UNITS") (pin "7") (pinfunction "7_7") (pintype "bidirectional"))
      (node (ref "T22") (pin "3") (pinfunction "C_3") (pintype "passive"))
    )
    (net (code "94") (name "Net-(T23-B)") (class "Default")
      (node (ref "R28") (pin "2") (pinfunction "2_2") (pintype "passive"))
      (node (ref "T23") (pin "2") (pinfunction "B_2") (pintype "passive"))
    )
    (net (code "95") (name "Net-(T23-C)") (class "Default")
      (node (ref "MINUTES_UNITS") (pin "8") (pinfunction "8_8") (pintype "bidirectional"))
      (node (ref "T23") (pin "3") (pinfunction "C_3") (pintype "passive"))
    )
    (net (code "96") (name "Net-(T24-B)") (class "Default")
      (node (ref "R29") (pin "2") (pinfunction "2_2") (pintype "passive"))
      (node (ref "T24") (pin "2") (pinfunction "B_2") (pintype "passive"))
    )
    (net (code "97") (name "Net-(T24-C)") (class "Default")
      (node (ref "MINUTES_UNITS") (pin "9") (pinfunction "9_9") (pintype "bidirectional"))
      (node (ref "T24") (pin "3") (pinfunction "C_3") (pintype "passive"))
    )
    (net (code "98") (name "Net-(T25-B)") (class "Default")
      (node (ref "R30") (pin "2") (pinfunction "2_2") (pintype "passive"))
      (node (ref "T25") (pin "2") (pinfunction "B_2") (pintype "passive"))
    )
    (net (code "99") (name "Net-(T25-C)") (class "Default")
      (node (ref "MINUTES_UNITS") (pin "0") (pinfunction "0_0") (pintype "bidirectional"))
      (node (ref "T25") (pin "3") (pinfunction "C_3") (pintype "passive"))
    )
    (net (code "100") (name "Net-(T26-B)") (class "Default")
      (node (ref "R36") (pin "2") (pinfunction "2_2") (pintype "passive"))
      (node (ref "T26") (pin "2") (pinfunction "B_2") (pintype "passive"))
    )
    (net (code "101") (name "Net-(T26-C)") (class "Default")
      (node (ref "MINUTES_TENS") (pin "0") (pinfunction "0_0") (pintype "bidirectional"))
      (node (ref "T26") (pin "3") (pinfunction "C_3") (pintype "passive"))
    )
    (net (code "102") (name "Net-(T27-B)") (class "Default")
      (node (ref "R31") (pin "2") (pinfunction "2_2") (pintype "passive"))
      (node (ref "T27") (pin "2") (pinfunction "B_2") (pintype "passive"))
    )
    (net (code "103") (name "Net-(T27-C)") (class "Default")
      (node (ref "MINUTES_TENS") (pin "1") (pinfunction "1_1") (pintype "bidirectional"))
      (node (ref "T27") (pin "3") (pinfunction "C_3") (pintype "passive"))
    )
    (net (code "104") (name "Net-(T28-B)") (class "Default")
      (node (ref "R32") (pin "2") (pinfunction "2_2") (pintype "passive"))
      (node (ref "T28") (pin "2") (pinfunction "B_2") (pintype "passive"))
    )
    (net (code "105") (name "Net-(T28-C)") (class "Default")
      (node (ref "MINUTES_TENS") (pin "2") (pinfunction "2_2") (pintype "bidirectional"))
      (node (ref "T28") (pin "3") (pinfunction "C_3") (pintype "passive"))
    )
    (net (code "106") (name "Net-(T29-B)") (class "Default")
      (node (ref "R33") (pin "2") (pinfunction "2_2") (pintype "passive"))
      (node (ref "T29") (pin "2") (pinfunction "B_2") (pintype "passive"))
    )
    (net (code "107") (name "Net-(T29-C)") (class "Default")
      (node (ref "MINUTES_TENS") (pin "3") (pinfunction "3_3") (pintype "bidirectional"))
      (node (ref "T29") (pin "3") (pinfunction "C_3") (pintype "passive"))
    )
    (net (code "108") (name "Net-(T30-B)") (class "Default")
      (node (ref "R34") (pin "2") (pinfunction "2_2") (pintype "passive"))
      (node (ref "T30") (pin "2") (pinfunction "B_2") (pintype "passive"))
    )
    (net (code "109") (name "Net-(T30-C)") (class "Default")
      (node (ref "MINUTES_TENS") (pin "4") (pinfunction "4_4") (pintype "bidirectional"))
      (node (ref "T30") (pin "3") (pinfunction "C_3") (pintype "passive"))
    )
    (net (code "110") (name "Net-(T31-B)") (class "Default")
      (node (ref "R35") (pin "2") (pinfunction "2_2") (pintype "passive"))
      (node (ref "T31") (pin "2") (pinfunction "B_2") (pintype "passive"))
    )
    (net (code "111") (name "Net-(T31-C)") (class "Default")
      (node (ref "MINUTES_TENS") (pin "5") (pinfunction "5_5") (pintype "bidirectional"))
      (node (ref "T31") (pin "3") (pinfunction "C_3") (pintype "passive"))
    )
    (net (code "112") (name "Net-(T32-B)") (class "Default")
      (node (ref "R39") (pin "2") (pinfunction "2_2") (pintype "passive"))
      (node (ref "T32") (pin "2") (pinfunction "B_2") (pintype "passive"))
    )
    (net (code "113") (name "Net-(T32-C)") (class "Default")
      (node (ref "HOURS_UNITS") (pin "1") (pinfunction "1_1") (pintype "bidirectional"))
      (node (ref "T32") (pin "3") (pinfunction "C_3") (pintype "passive"))
    )
    (net (code "114") (name "Net-(T33-B)") (class "Default")
      (node (ref "R40") (pin "2") (pinfunction "2_2") (pintype "passive"))
      (node (ref "T33") (pin "2") (pinfunction "B_2") (pintype "passive"))
    )
    (net (code "115") (name "Net-(T33-C)") (class "Default")
      (node (ref "HOURS_UNITS") (pin "2") (pinfunction "2_2") (pintype "bidirectional"))
      (node (ref "T33") (pin "3") (pinfunction "C_3") (pintype "passive"))
    )
    (net (code "116") (name "Net-(T34-B)") (class "Default")
      (node (ref "R41") (pin "2") (pinfunction "2_2") (pintype "passive"))
      (node (ref "T34") (pin "2") (pinfunction "B_2") (pintype "passive"))
    )
    (net (code "117") (name "Net-(T34-C)") (class "Default")
      (node (ref "HOURS_UNITS") (pin "3") (pinfunction "3_3") (pintype "bidirectional"))
      (node (ref "T34") (pin "3") (pinfunction "C_3") (pintype "passive"))
    )
    (net (code "118") (name "Net-(T35-B)") (class "Default")
      (node (ref "R42") (pin "2") (pinfunction "2_2") (pintype "passive"))
      (node (ref "T35") (pin "2") (pinfunction "B_2") (pintype "passive"))
    )
    (net (code "119") (name "Net-(T35-C)") (class "Default")
      (node (ref "HOURS_UNITS") (pin "4") (pinfunction "4_4") (pintype "bidirectional"))
      (node (ref "T35") (pin "3") (pinfunction "C_3") (pintype "passive"))
    )
    (net (code "120") (name "Net-(T36-B)") (class "Default")
      (node (ref "R43") (pin "2") (pinfunction "2_2") (pintype "passive"))
      (node (ref "T36") (pin "2") (pinfunction "B_2") (pintype "passive"))
    )
    (net (code "121") (name "Net-(T36-C)") (class "Default")
      (node (ref "HOURS_UNITS") (pin "5") (pinfunction "5_5") (pintype "bidirectional"))
      (node (ref "T36") (pin "3") (pinfunction "C_3") (pintype "passive"))
    )
    (net (code "122") (name "Net-(T37-B)") (class "Default")
      (node (ref "R44") (pin "2") (pinfunction "2_2") (pintype "passive"))
      (node (ref "T37") (pin "2") (pinfunction "B_2") (pintype "passive"))
    )
    (net (code "123") (name "Net-(T37-C)") (class "Default")
      (node (ref "HOURS_UNITS") (pin "6") (pinfunction "6_6") (pintype "bidirectional"))
      (node (ref "T37") (pin "3") (pinfunction "C_3") (pintype "passive"))
    )
    (net (code "124") (name "Net-(T38-B)") (class "Default")
      (node (ref "R45") (pin "2") (pinfunction "2_2") (pintype "passive"))
      (node (ref "T38") (pin "2") (pinfunction "B_2") (pintype "passive"))
    )
    (net (code "125") (name "Net-(T38-C)") (class "Default")
      (node (ref "HOURS_UNITS") (pin "7") (pinfunction "7_7") (pintype "bidirectional"))
      (node (ref "T38") (pin "3") (pinfunction "C_3") (pintype "passive"))
    )
    (net (code "126") (name "Net-(T39-B)") (class "Default")
      (node (ref "R46") (pin "2") (pinfunction "2_2") (pintype "passive"))
      (node (ref "T39") (pin "2") (pinfunction "B_2") (pintype "passive"))
    )
    (net (code "127") (name "Net-(T39-C)") (class "Default")
      (node (ref "HOURS_UNITS") (pin "8") (pinfunction "8_8") (pintype "bidirectional"))
      (node (ref "T39") (pin "3") (pinfunction "C_3") (pintype "passive"))
    )
    (net (code "128") (name "Net-(T40-B)") (class "Default")
      (node (ref "R47") (pin "2") (pinfunction "2_2") (pintype "passive"))
      (node (ref "T40") (pin "2") (pinfunction "B_2") (pintype "passive"))
    )
    (net (code "129") (name "Net-(T40-C)") (class "Default")
      (node (ref "HOURS_UNITS") (pin "9") (pinfunction "9_9") (pintype "bidirectional"))
      (node (ref "T40") (pin "3") (pinfunction "C_3") (pintype "passive"))
    )
    (net (code "130") (name "Net-(T41-B)") (class "Default")
      (node (ref "R48") (pin "2") (pinfunction "2_2") (pintype "passive"))
      (node (ref "T41") (pin "2") (pinfunction "B_2") (pintype "passive"))
    )
    (net (code "131") (name "Net-(T41-C)") (class "Default")
      (node (ref "HOURS_UNITS") (pin "0") (pinfunction "0_0") (pintype "bidirectional"))
      (node (ref "T41") (pin "3") (pinfunction "C_3") (pintype "passive"))
    )
    (net (code "132") (name "Net-(T42-B)") (class "Default")
      (node (ref "R54") (pin "2") (pinfunction "2_2") (pintype "passive"))
      (node (ref "T42") (pin "2") (pinfunction "B_2") (pintype "passive"))
    )
    (net (code "133") (name "Net-(T42-C)") (class "Default")
      (node (ref "HOURS_TENS") (pin "0") (pinfunction "0_0") (pintype "bidirectional"))
      (node (ref "T42") (pin "3") (pinfunction "C_3") (pintype "passive"))
    )
    (net (code "134") (name "Net-(T43-B)") (class "Default")
      (node (ref "R49") (pin "2") (pinfunction "2_2") (pintype "passive"))
      (node (ref "T43") (pin "2") (pinfunction "B_2") (pintype "passive"))
    )
    (net (code "135") (name "Net-(T43-C)") (class "Default")
      (node (ref "HOURS_TENS") (pin "1") (pinfunction "1_1") (pintype "bidirectional"))
      (node (ref "T43") (pin "3") (pinfunction "C_3") (pintype "passive"))
    )
    (net (code "136") (name "Net-(T44-B)") (class "Default")
      (node (ref "R50") (pin "2") (pinfunction "2_2") (pintype "passive"))
      (node (ref "T44") (pin "2") (pinfunction "B_2") (pintype "passive"))
    )
    (net (code "137") (name "Net-(T44-C)") (class "Default")
      (node (ref "HOURS_TENS") (pin "2") (pinfunction "2_2") (pintype "bidirectional"))
      (node (ref "T44") (pin "3") (pinfunction "C_3") (pintype "passive"))
    )
    (net (code "138") (name "RESET_HOURS") (class "Default")
      (node (ref "D16") (pin "A") (pinfunction "A_A") (pintype "passive"))
      (node (ref "D9") (pin "A") (pinfunction "A_A") (pintype "passive"))
      (node (ref "IC7_AND") (pin "3") (pinfunction "O_3") (pintype "output"))
    )
    (net (code "139") (name "SEC_0") (class "Default")
      (node (ref "IC1_SECONDS_UNITS") (pin "3") (pinfunction "Q0_3") (pintype "output"))
      (node (ref "R12") (pin "1") (pinfunction "1_1") (pintype "passive"))
    )
    (net (code "140") (name "SEC_1") (class "Default")
      (node (ref "IC1_SECONDS_UNITS") (pin "2") (pinfunction "Q1_2") (pintype "output"))
      (node (ref "R3") (pin "1") (pinfunction "1_1") (pintype "passive"))
    )
    (net (code "141") (name "SEC_2") (class "Default")
      (node (ref "IC1_SECONDS_UNITS") (pin "4") (pinfunction "Q2_4") (pintype "output"))
      (node (ref "R4") (pin "1") (pinfunction "1_1") (pintype "passive"))
    )
    (net (code "142") (name "SEC_3") (class "Default")
      (node (ref "IC1_SECONDS_UNITS") (pin "7") (pinfunction "Q3_7") (pintype "output"))
      (node (ref "R5") (pin "1") (pinfunction "1_1") (pintype "passive"))
    )
    (net (code "143") (name "SEC_4") (class "Default")
      (node (ref "IC1_SECONDS_UNITS") (pin "10") (pinfunction "Q4_10") (pintype "output"))
      (node (ref "R6") (pin "1") (pinfunction "1_1") (pintype "passive"))
    )
    (net (code "144") (name "SEC_5") (class "Default")
      (node (ref "IC1_SECONDS_UNITS") (pin "1") (pinfunction "Q5_1") (pintype "output"))
      (node (ref "R7") (pin "1") (pinfunction "1_1") (pintype "passive"))
    )
    (net (code "145") (name "SEC_6") (class "Default")
      (node (ref "IC1_SECONDS_UNITS") (pin "5") (pinfunction "Q6_5") (pintype "output"))
      (node (ref "R8") (pin "1") (pinfunction "1_1") (pintype "passive"))
    )
    (net (code "146") (name "SEC_7") (class "Default")
      (node (ref "IC1_SECONDS_UNITS") (pin "6") (pinfunction "Q7_6") (pintype "output"))
      (node (ref "R9") (pin "1") (pinfunction "1_1") (pintype "passive"))
    )
    (net (code "147") (name "SEC_8") (class "Default")
      (node (ref "IC1_SECONDS_UNITS") (pin "9") (pinfunction "Q8_9") (pintype "output"))
      (node (ref "R10") (pin "1") (pinfunction "1_1") (pintype "passive"))
    )
    (net (code "148") (name "SEC_9") (class "Default")
      (node (ref "IC1_SECONDS_UNITS") (pin "11") (pinfunction "Q9_11") (pintype "output"))
      (node (ref "R11") (pin "1") (pinfunction "1_1") (pintype "passive"))
    )
    (net (code "149") (name "THOURS_0") (class "Default")
      (node (ref "IC6_HOURS_TENS") (pin "3") (pinfunction "Q0_3") (pintype "output"))
      (node (ref "R54") (pin "1") (pinfunction "1_1") (pintype "passive"))
    )
    (net (code "150") (name "THOURS_1") (class "Default")
      (node (ref "IC6_HOURS_TENS") (pin "2") (pinfunction "Q1_2") (pintype "output"))
      (node (ref "R49") (pin "1") (pinfunction "1_1") (pintype "passive"))
    )
    (net (code "151") (name "THOURS_2") (class "Default")
      (node (ref "IC6_HOURS_TENS") (pin "4") (pinfunction "Q2_4") (pintype "output"))
      (node (ref "IC7_AND") (pin "2") (pinfunction "I1_2") (pintype "input"))
      (node (ref "R50") (pin "1") (pinfunction "1_1") (pintype "passive"))
    )
    (net (code "152") (name "TIME_REFERENCE") (class "Default")
      (node (ref "CON_TIME_REF") (pin "P$1") (pinfunction "P$1_P$1") (pintype "bidirectional"))
      (node (ref "IC1_SECONDS_UNITS") (pin "14") (pinfunction "CLK_14") (pintype "input"))
    )
    (net (code "153") (name "TMIN_0") (class "Default")
      (node (ref "IC4_MINUTES_TENS") (pin "3") (pinfunction "Q0_3") (pintype "output"))
      (node (ref "R36") (pin "1") (pinfunction "1_1") (pintype "passive"))
    )
    (net (code "154") (name "TMIN_1") (class "Default")
      (node (ref "IC4_MINUTES_TENS") (pin "2") (pinfunction "Q1_2") (pintype "output"))
      (node (ref "R31") (pin "1") (pinfunction "1_1") (pintype "passive"))
    )
    (net (code "155") (name "TMIN_2") (class "Default")
      (node (ref "IC4_MINUTES_TENS") (pin "4") (pinfunction "Q2_4") (pintype "output"))
      (node (ref "R32") (pin "1") (pinfunction "1_1") (pintype "passive"))
    )
    (net (code "156") (name "TMIN_3") (class "Default")
      (node (ref "IC4_MINUTES_TENS") (pin "7") (pinfunction "Q3_7") (pintype "output"))
      (node (ref "R33") (pin "1") (pinfunction "1_1") (pintype "passive"))
    )
    (net (code "157") (name "TMIN_4") (class "Default")
      (node (ref "IC4_MINUTES_TENS") (pin "10") (pinfunction "Q4_10") (pintype "output"))
      (node (ref "R34") (pin "1") (pinfunction "1_1") (pintype "passive"))
    )
    (net (code "158") (name "TMIN_5") (class "Default")
      (node (ref "IC4_MINUTES_TENS") (pin "1") (pinfunction "Q5_1") (pintype "output"))
      (node (ref "R35") (pin "1") (pinfunction "1_1") (pintype "passive"))
    )
    (net (code "159") (name "TSEC_0") (class "Default")
      (node (ref "IC2_SECONDS_TENS") (pin "3") (pinfunction "Q0_3") (pintype "output"))
      (node (ref "R18") (pin "1") (pinfunction "1_1") (pintype "passive"))
    )
    (net (code "160") (name "TSEC_1") (class "Default")
      (node (ref "IC2_SECONDS_TENS") (pin "2") (pinfunction "Q1_2") (pintype "output"))
      (node (ref "R13") (pin "1") (pinfunction "1_1") (pintype "passive"))
    )
    (net (code "161") (name "TSEC_2") (class "Default")
      (node (ref "IC2_SECONDS_TENS") (pin "4") (pinfunction "Q2_4") (pintype "output"))
      (node (ref "R14") (pin "1") (pinfunction "1_1") (pintype "passive"))
    )
    (net (code "162") (name "TSEC_3") (class "Default")
      (node (ref "IC2_SECONDS_TENS") (pin "7") (pinfunction "Q3_7") (pintype "output"))
      (node (ref "R15") (pin "1") (pinfunction "1_1") (pintype "passive"))
    )
    (net (code "163") (name "TSEC_4") (class "Default")
      (node (ref "IC2_SECONDS_TENS") (pin "10") (pinfunction "Q4_10") (pintype "output"))
      (node (ref "R16") (pin "1") (pinfunction "1_1") (pintype "passive"))
    )
    (net (code "164") (name "TSEC_5") (class "Default")
      (node (ref "IC2_SECONDS_TENS") (pin "1") (pinfunction "Q5_1") (pintype "output"))
      (node (ref "R17") (pin "1") (pinfunction "1_1") (pintype "passive"))
    )
    (net (code "165") (name "VCC") (class "Default")
      (node (ref "C1") (pin "1") (pinfunction "1_1") (pintype "passive"))
      (node (ref "C2") (pin "1") (pinfunction "1_1") (pintype "passive"))
      (node (ref "C3") (pin "1") (pinfunction "1_1") (pintype "passive"))
      (node (ref "C4") (pin "1") (pinfunction "1_1") (pintype "passive"))
      (node (ref "C5") (pin "1") (pinfunction "1_1") (pintype "passive"))
      (node (ref "C6") (pin "1") (pinfunction "1_1") (pintype "passive"))
      (node (ref "C7") (pin "1") (pinfunction "1_1") (pintype "passive"))
      (node (ref "C8") (pin "1") (pinfunction "1_1") (pintype "passive"))
      (node (ref "C9") (pin "1") (pinfunction "1_1") (pintype "passive"))
      (node (ref "CON_LOGIC_POWER") (pin "P$1") (pinfunction "P$1_P$1") (pintype "bidirectional"))
      (node (ref "IC1_SECONDS_UNITS") (pin "16") (pinfunction "VDD_16") (pintype "power_in"))
      (node (ref "IC2_SECONDS_TENS") (pin "16") (pinfunction "VDD_16") (pintype "power_in"))
      (node (ref "IC3_MINUTES_UNITS") (pin "16") (pinfunction "VDD_16") (pintype "power_in"))
      (node (ref "IC4_MINUTES_TENS") (pin "16") (pinfunction "VDD_16") (pintype "power_in"))
      (node (ref "IC5_HOURS_UNITS") (pin "16") (pinfunction "VDD_16") (pintype "power_in"))
      (node (ref "IC6_HOURS_TENS") (pin "16") (pinfunction "VDD_16") (pintype "power_in"))
      (node (ref "IC7_AND") (pin "14") (pinfunction "VDD_14") (pintype "power_in"))
      (node (ref "S1_RESET") (pin "1") (pinfunction "1_1") (pintype "passive"))
      (node (ref "S2_MINUTE") (pin "3") (pinfunction "2_3") (pintype "passive"))
      (node (ref "S3_HOUR") (pin "3") (pinfunction "2_3") (pintype "passive"))
    )
    (net (code "166") (name "VHIGH") (class "Default")
      (node (ref "CON_HIGH_VOLTAGE") (pin "P$1") (pinfunction "P$1_P$1") (pintype "bidirectional"))
      (node (ref "R1") (pin "2") (pinfunction "2_2") (pintype "passive"))
      (node (ref "R19") (pin "2") (pinfunction "2_2") (pintype "passive"))
      (node (ref "R2") (pin "2") (pinfunction "2_2") (pintype "passive"))
      (node (ref "R20") (pin "2") (pinfunction "2_2") (pintype "passive"))
      (node (ref "R37") (pin "2") (pinfunction "2_2") (pintype "passive"))
      (node (ref "R38") (pin "2") (pinfunction "2_2") (pintype "passive"))
      (node (ref "R60") (pin "1") (pinfunction "1_1") (pintype "passive"))
      (node (ref "R61") (pin "1") (pinfunction "1_1") (pintype "passive"))
    )
    (net (code "167") (name "unconnected-(HOURS_TENS-Pad3)") (class "Default")
      (node (ref "HOURS_TENS") (pin "3") (pinfunction "3_3") (pintype "bidirectional"))
    )
    (net (code "168") (name "unconnected-(HOURS_TENS-Pad4)") (class "Default")
      (node (ref "HOURS_TENS") (pin "4") (pinfunction "4_4") (pintype "bidirectional"))
    )
    (net (code "169") (name "unconnected-(HOURS_TENS-Pad5)") (class "Default")
      (node (ref "HOURS_TENS") (pin "5") (pinfunction "5_5") (pintype "bidirectional"))
    )
    (net (code "170") (name "unconnected-(HOURS_TENS-Pad6)") (class "Default")
      (node (ref "HOURS_TENS") (pin "6") (pinfunction "6_6") (pintype "bidirectional"))
    )
    (net (code "171") (name "unconnected-(HOURS_TENS-Pad7)") (class "Default")
      (node (ref "HOURS_TENS") (pin "7") (pinfunction "7_7") (pintype "bidirectional"))
    )
    (net (code "172") (name "unconnected-(HOURS_TENS-Pad8)") (class "Default")
      (node (ref "HOURS_TENS") (pin "8") (pinfunction "8_8") (pintype "bidirectional"))
    )
    (net (code "173") (name "unconnected-(HOURS_TENS-Pad9)") (class "Default")
      (node (ref "HOURS_TENS") (pin "9") (pinfunction "9_9") (pintype "bidirectional"))
    )
    (net (code "174") (name "unconnected-(HOURS_TENS-PadLHDP)") (class "Default")
      (node (ref "HOURS_TENS") (pin "LHDP") (pinfunction "LHDP_LHDP") (pintype "bidirectional"))
    )
    (net (code "175") (name "unconnected-(HOURS_TENS-PadRHDP)") (class "Default")
      (node (ref "HOURS_TENS") (pin "RHDP") (pinfunction "RHDP_RHDP") (pintype "bidirectional"))
    )
    (net (code "176") (name "unconnected-(HOURS_UNITS-PadLHDP)") (class "Default")
      (node (ref "HOURS_UNITS") (pin "LHDP") (pinfunction "LHDP_LHDP") (pintype "bidirectional"))
    )
    (net (code "177") (name "unconnected-(HOURS_UNITS-PadRHDP)") (class "Default")
      (node (ref "HOURS_UNITS") (pin "RHDP") (pinfunction "RHDP_RHDP") (pintype "bidirectional"))
    )
    (net (code "178") (name "unconnected-(IC2_SECONDS_TENSA-CO-Pad12)") (class "Default")
      (node (ref "IC2_SECONDS_TENS") (pin "12") (pinfunction "CO_12") (pintype "output"))
    )
    (net (code "179") (name "unconnected-(IC2_SECONDS_TENSA-Q7-Pad6)") (class "Default")
      (node (ref "IC2_SECONDS_TENS") (pin "6") (pinfunction "Q7_6") (pintype "output"))
    )
    (net (code "180") (name "unconnected-(IC2_SECONDS_TENSA-Q8-Pad9)") (class "Default")
      (node (ref "IC2_SECONDS_TENS") (pin "9") (pinfunction "Q8_9") (pintype "output"))
    )
    (net (code "181") (name "unconnected-(IC2_SECONDS_TENSA-Q9-Pad11)") (class "Default")
      (node (ref "IC2_SECONDS_TENS") (pin "11") (pinfunction "Q9_11") (pintype "output"))
    )
    (net (code "182") (name "unconnected-(IC4_MINUTES_TENSA-CO-Pad12)") (class "Default")
      (node (ref "IC4_MINUTES_TENS") (pin "12") (pinfunction "CO_12") (pintype "output"))
    )
    (net (code "183") (name "unconnected-(IC4_MINUTES_TENSA-Q7-Pad6)") (class "Default")
      (node (ref "IC4_MINUTES_TENS") (pin "6") (pinfunction "Q7_6") (pintype "output"))
    )
    (net (code "184") (name "unconnected-(IC4_MINUTES_TENSA-Q8-Pad9)") (class "Default")
      (node (ref "IC4_MINUTES_TENS") (pin "9") (pinfunction "Q8_9") (pintype "output"))
    )
    (net (code "185") (name "unconnected-(IC4_MINUTES_TENSA-Q9-Pad11)") (class "Default")
      (node (ref "IC4_MINUTES_TENS") (pin "11") (pinfunction "Q9_11") (pintype "output"))
    )
    (net (code "186") (name "unconnected-(IC6_HOURS_TENSA-CO-Pad12)") (class "Default")
      (node (ref "IC6_HOURS_TENS") (pin "12") (pinfunction "CO_12") (pintype "output"))
    )
    (net (code "187") (name "unconnected-(IC6_HOURS_TENSA-Q3-Pad7)") (class "Default")
      (node (ref "IC6_HOURS_TENS") (pin "7") (pinfunction "Q3_7") (pintype "output"))
    )
    (net (code "188") (name "unconnected-(IC6_HOURS_TENSA-Q4-Pad10)") (class "Default")
      (node (ref "IC6_HOURS_TENS") (pin "10") (pinfunction "Q4_10") (pintype "output"))
    )
    (net (code "189") (name "unconnected-(IC6_HOURS_TENSA-Q5-Pad1)") (class "Default")
      (node (ref "IC6_HOURS_TENS") (pin "1") (pinfunction "Q5_1") (pintype "output"))
    )
    (net (code "190") (name "unconnected-(IC6_HOURS_TENSA-Q6-Pad5)") (class "Default")
      (node (ref "IC6_HOURS_TENS") (pin "5") (pinfunction "Q6_5") (pintype "output"))
    )
    (net (code "191") (name "unconnected-(IC6_HOURS_TENSA-Q7-Pad6)") (class "Default")
      (node (ref "IC6_HOURS_TENS") (pin "6") (pinfunction "Q7_6") (pintype "output"))
    )
    (net (code "192") (name "unconnected-(IC6_HOURS_TENSA-Q8-Pad9)") (class "Default")
      (node (ref "IC6_HOURS_TENS") (pin "9") (pinfunction "Q8_9") (pintype "output"))
    )
    (net (code "193") (name "unconnected-(IC6_HOURS_TENSA-Q9-Pad11)") (class "Default")
      (node (ref "IC6_HOURS_TENS") (pin "11") (pinfunction "Q9_11") (pintype "output"))
    )
    (net (code "194") (name "unconnected-(MINUTES_TENS-Pad6)") (class "Default")
      (node (ref "MINUTES_TENS") (pin "6") (pinfunction "6_6") (pintype "bidirectional"))
    )
    (net (code "195") (name "unconnected-(MINUTES_TENS-Pad7)") (class "Default")
      (node (ref "MINUTES_TENS") (pin "7") (pinfunction "7_7") (pintype "bidirectional"))
    )
    (net (code "196") (name "unconnected-(MINUTES_TENS-Pad8)") (class "Default")
      (node (ref "MINUTES_TENS") (pin "8") (pinfunction "8_8") (pintype "bidirectional"))
    )
    (net (code "197") (name "unconnected-(MINUTES_TENS-Pad9)") (class "Default")
      (node (ref "MINUTES_TENS") (pin "9") (pinfunction "9_9") (pintype "bidirectional"))
    )
    (net (code "198") (name "unconnected-(MINUTES_TENS-PadLHDP)") (class "Default")
      (node (ref "MINUTES_TENS") (pin "LHDP") (pinfunction "LHDP_LHDP") (pintype "bidirectional"))
    )
    (net (code "199") (name "unconnected-(MINUTES_TENS-PadRHDP)") (class "Default")
      (node (ref "MINUTES_TENS") (pin "RHDP") (pinfunction "RHDP_RHDP") (pintype "bidirectional"))
    )
    (net (code "200") (name "unconnected-(MINUTES_UNITS-PadLHDP)") (class "Default")
      (node (ref "MINUTES_UNITS") (pin "LHDP") (pinfunction "LHDP_LHDP") (pintype "bidirectional"))
    )
    (net (code "201") (name "unconnected-(MINUTES_UNITS-PadRHDP)") (class "Default")
      (node (ref "MINUTES_UNITS") (pin "RHDP") (pinfunction "RHDP_RHDP") (pintype "bidirectional"))
    )
    (net (code "202") (name "unconnected-(SECONDS_TENS-Pad6)") (class "Default")
      (node (ref "SECONDS_TENS") (pin "6") (pinfunction "6_6") (pintype "bidirectional"))
    )
    (net (code "203") (name "unconnected-(SECONDS_TENS-Pad7)") (class "Default")
      (node (ref "SECONDS_TENS") (pin "7") (pinfunction "7_7") (pintype "bidirectional"))
    )
    (net (code "204") (name "unconnected-(SECONDS_TENS-Pad8)") (class "Default")
      (node (ref "SECONDS_TENS") (pin "8") (pinfunction "8_8") (pintype "bidirectional"))
    )
    (net (code "205") (name "unconnected-(SECONDS_TENS-Pad9)") (class "Default")
      (node (ref "SECONDS_TENS") (pin "9") (pinfunction "9_9") (pintype "bidirectional"))
    )
    (net (code "206") (name "unconnected-(SECONDS_TENS-PadLHDP)") (class "Default")
      (node (ref "SECONDS_TENS") (pin "LHDP") (pinfunction "LHDP_LHDP") (pintype "bidirectional"))
    )
    (net (code "207") (name "unconnected-(SECONDS_TENS-PadRHDP)") (class "Default")
      (node (ref "SECONDS_TENS") (pin "RHDP") (pinfunction "RHDP_RHDP") (pintype "bidirectional"))
    )
    (net (code "208") (name "unconnected-(SECONDS_UNITS-PadLHDP)") (class "Default")
      (node (ref "SECONDS_UNITS") (pin "LHDP") (pinfunction "LHDP_LHDP") (pintype "bidirectional"))
    )
    (net (code "209") (name "unconnected-(SECONDS_UNITS-PadRHDP)") (class "Default")
      (node (ref "SECONDS_UNITS") (pin "RHDP") (pinfunction "RHDP_RHDP") (pintype "bidirectional"))
    )
  )
)
